# flipchip.net
KiCad netlist of a schematic drawn in EAGLE
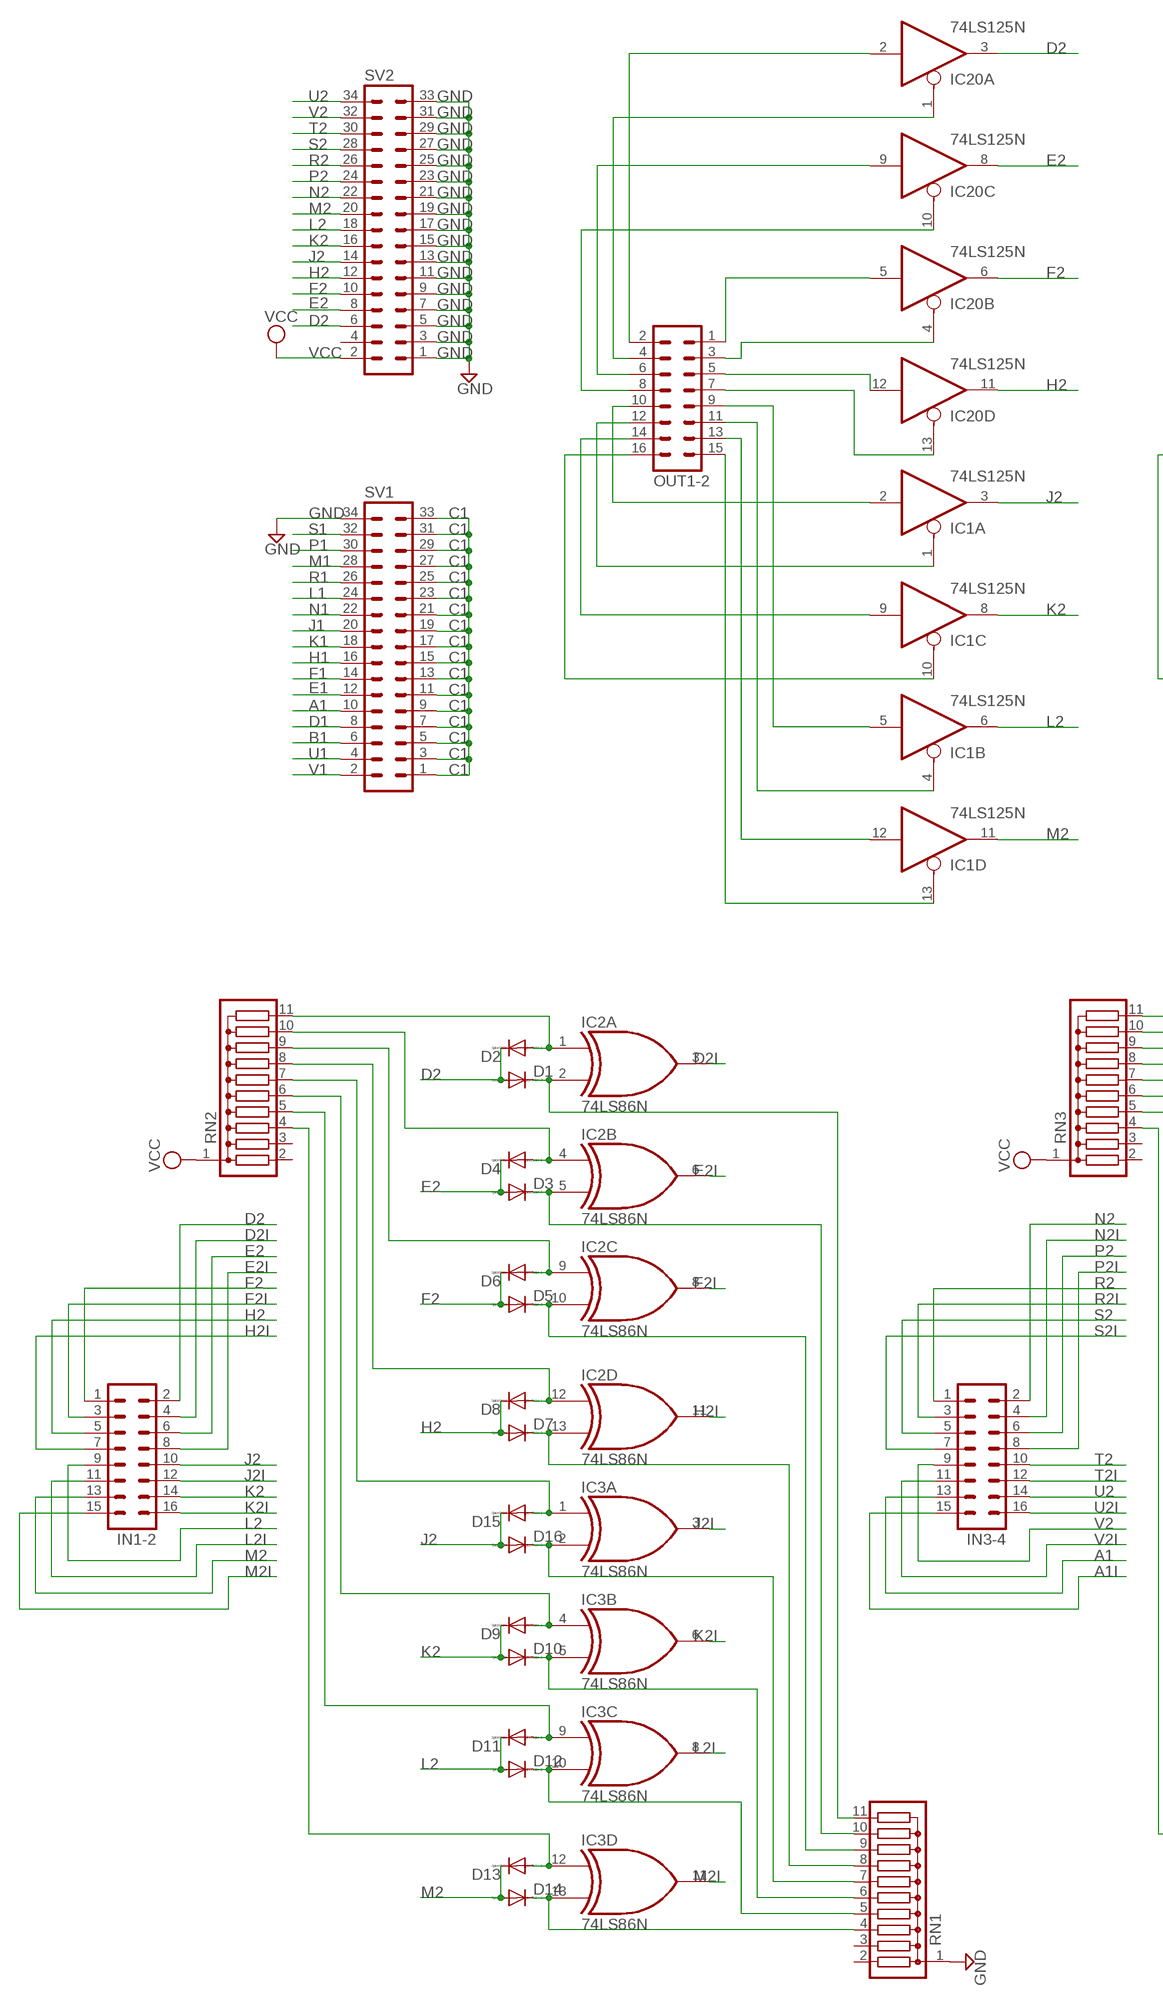
[diagram p0: schematic, sheet 1, part 1 of 2]
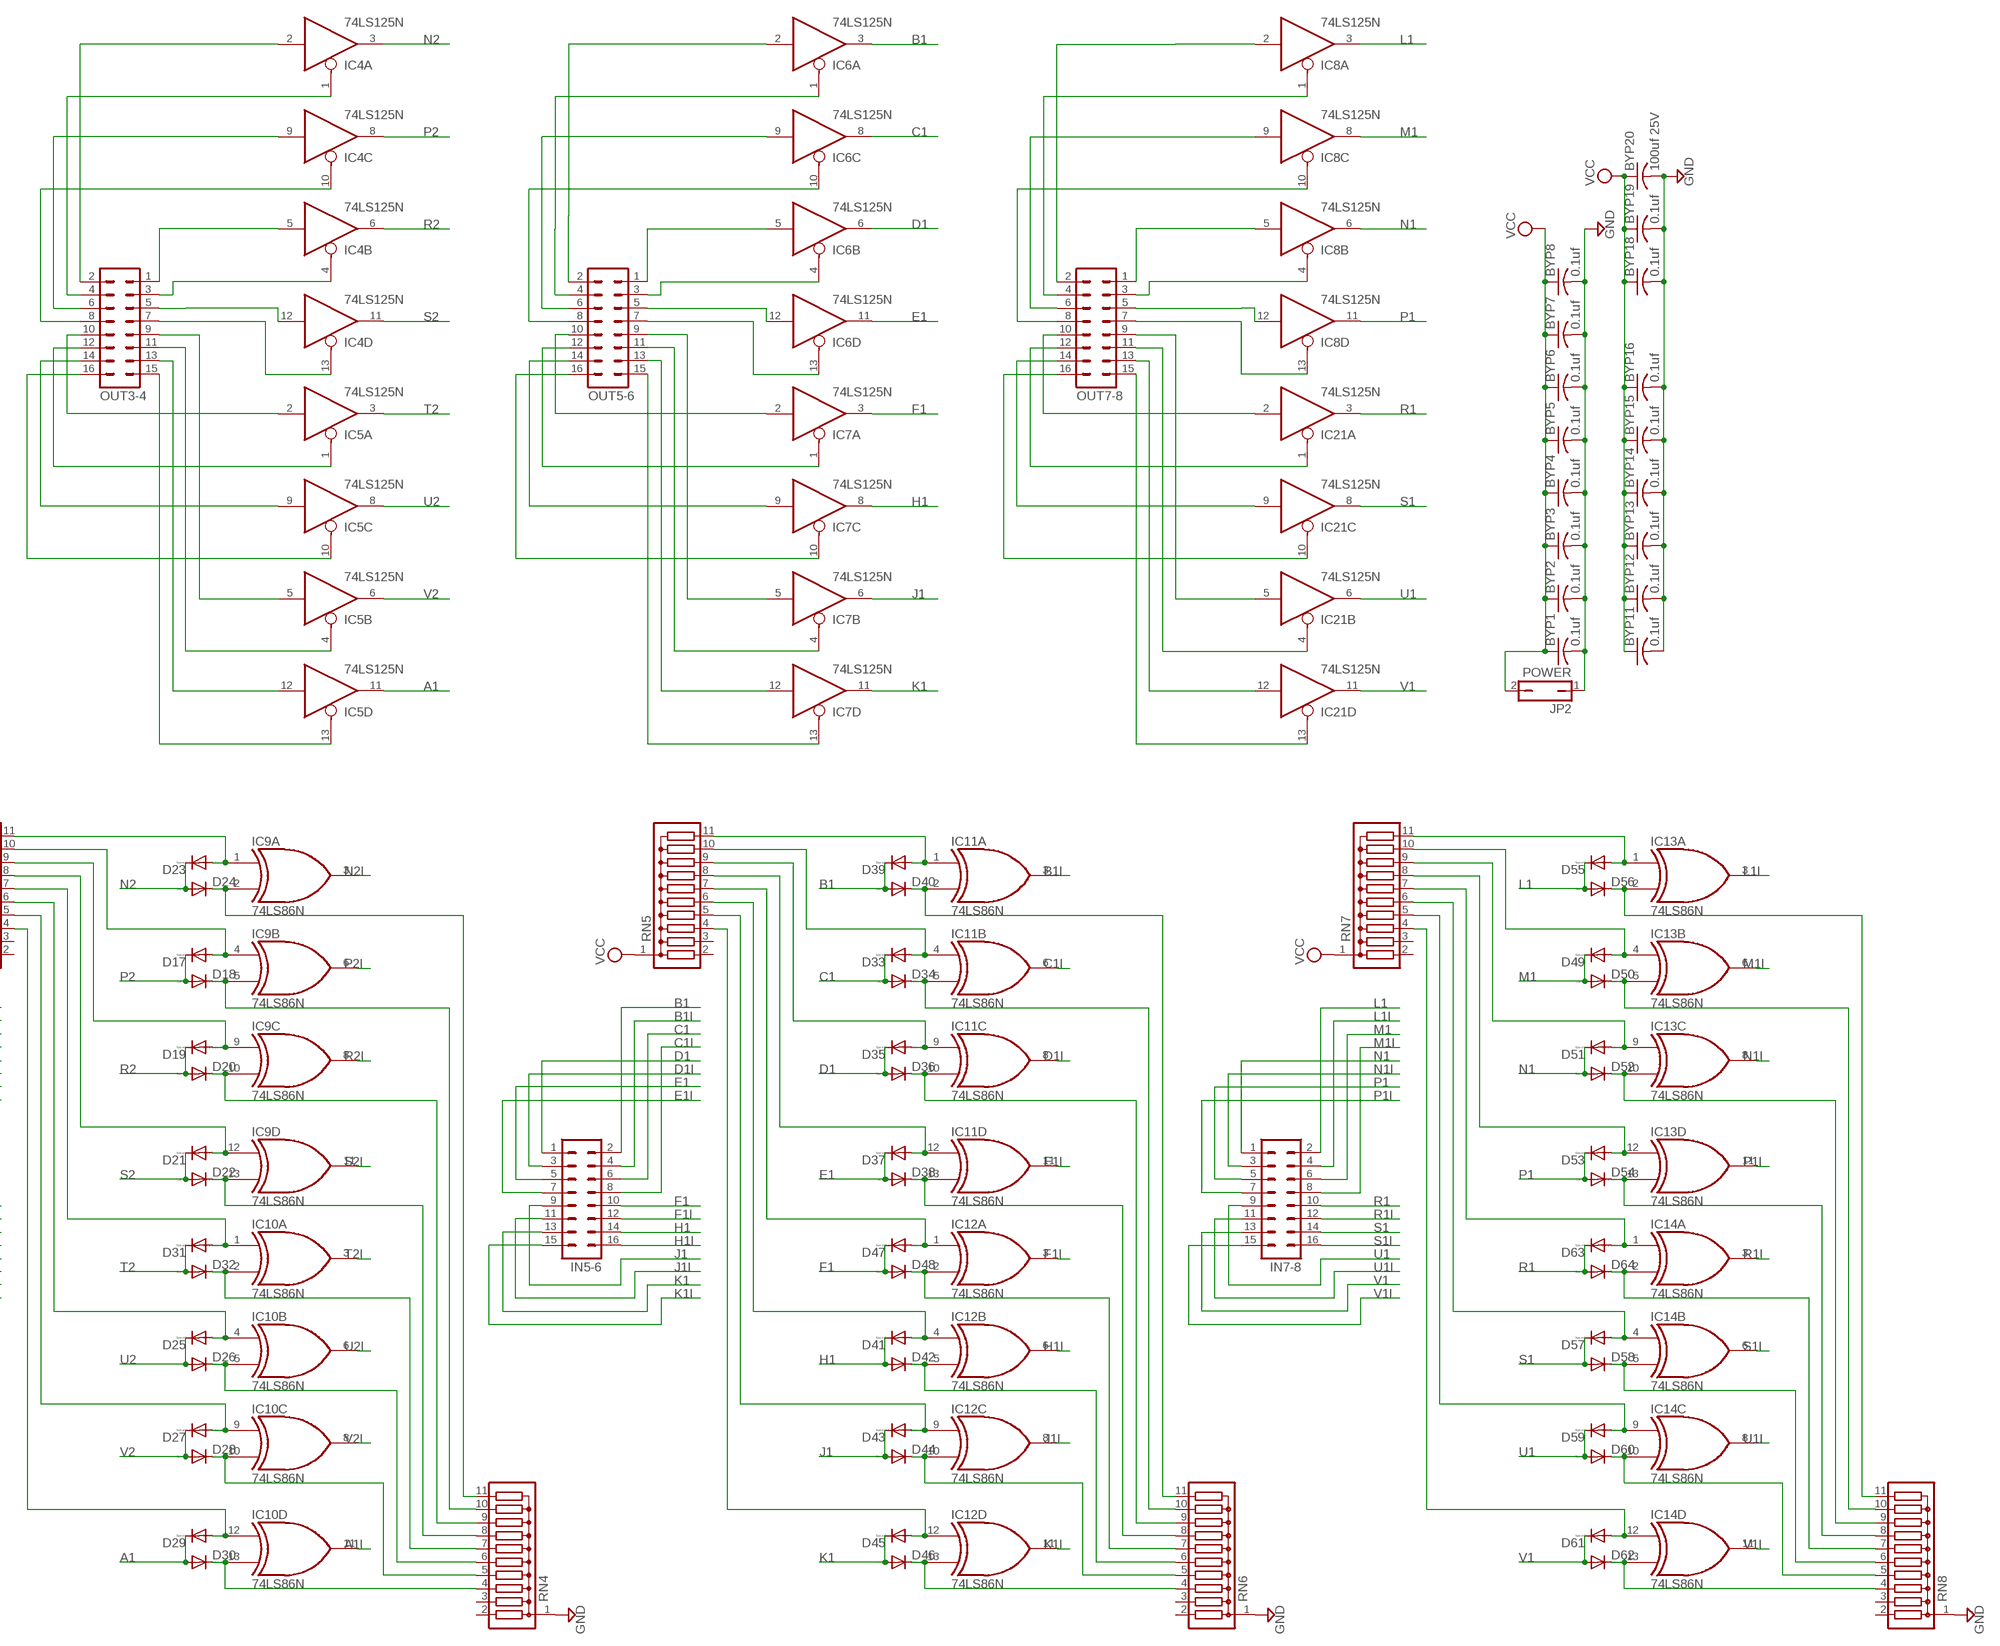
[diagram p1: schematic, sheet 1, part 2 of 2]

(export (version "E")
  (design (tool "Eeschema 10.0.6"))
  (components
    (comp (ref "BYP1")
      (value "0.1uf")
      (footprint "eagle-import:C050-025X075")
      (libsource (lib "eagle-import") (part "C-US050-025X075"))
    )
    (comp (ref "BYP2")
      (value "0.1uf")
      (footprint "eagle-import:C050-025X075")
      (libsource (lib "eagle-import") (part "C-US050-025X075"))
    )
    (comp (ref "BYP3")
      (value "0.1uf")
      (footprint "eagle-import:C050-025X075")
      (libsource (lib "eagle-import") (part "C-US050-025X075"))
    )
    (comp (ref "BYP4")
      (value "0.1uf")
      (footprint "eagle-import:C050-025X075")
      (libsource (lib "eagle-import") (part "C-US050-025X075"))
    )
    (comp (ref "BYP5")
      (value "0.1uf")
      (footprint "eagle-import:C050-025X075")
      (libsource (lib "eagle-import") (part "C-US050-025X075"))
    )
    (comp (ref "BYP6")
      (value "0.1uf")
      (footprint "eagle-import:C050-025X075")
      (libsource (lib "eagle-import") (part "C-US050-025X075"))
    )
    (comp (ref "BYP7")
      (value "0.1uf")
      (footprint "eagle-import:C050-025X075")
      (libsource (lib "eagle-import") (part "C-US050-025X075"))
    )
    (comp (ref "BYP8")
      (value "0.1uf")
      (footprint "eagle-import:C050-025X075")
      (libsource (lib "eagle-import") (part "C-US050-025X075"))
    )
    (comp (ref "BYP11")
      (value "0.1uf")
      (footprint "eagle-import:C050-025X075")
      (libsource (lib "eagle-import") (part "C-US050-025X075"))
    )
    (comp (ref "BYP12")
      (value "0.1uf")
      (footprint "eagle-import:C050-025X075")
      (libsource (lib "eagle-import") (part "C-US050-025X075"))
    )
    (comp (ref "BYP13")
      (value "0.1uf")
      (footprint "eagle-import:C050-025X075")
      (libsource (lib "eagle-import") (part "C-US050-025X075"))
    )
    (comp (ref "BYP14")
      (value "0.1uf")
      (footprint "eagle-import:C050-025X075")
      (libsource (lib "eagle-import") (part "C-US050-025X075"))
    )
    (comp (ref "BYP15")
      (value "0.1uf")
      (footprint "eagle-import:C050-025X075")
      (libsource (lib "eagle-import") (part "C-US050-025X075"))
    )
    (comp (ref "BYP16")
      (value "0.1uf")
      (footprint "eagle-import:C050-025X075")
      (libsource (lib "eagle-import") (part "C-US050-025X075"))
    )
    (comp (ref "BYP18")
      (value "0.1uf")
      (footprint "eagle-import:C050-025X075")
      (libsource (lib "eagle-import") (part "C-US050-025X075"))
    )
    (comp (ref "BYP19")
      (value "0.1uf")
      (footprint "eagle-import:C050-025X075")
      (libsource (lib "eagle-import") (part "C-US050-025X075"))
    )
    (comp (ref "BYP20")
      (value "100uf 25V")
      (footprint "eagle-import:C150-064X183")
      (libsource (lib "eagle-import") (part "C-US150-064X183"))
    )
    (comp (ref "D1")
      (value "DIODE-D-2.5")
      (footprint "eagle-import:D-2.5")
      (libsource (lib "eagle-import") (part "DIODE-D-2.5"))
    )
    (comp (ref "D2")
      (value "DIODE-D-2.5")
      (footprint "eagle-import:D-2.5")
      (libsource (lib "eagle-import") (part "DIODE-D-2.5"))
    )
    (comp (ref "D3")
      (value "DIODE-D-2.5")
      (footprint "eagle-import:D-2.5")
      (libsource (lib "eagle-import") (part "DIODE-D-2.5"))
    )
    (comp (ref "D4")
      (value "DIODE-D-2.5")
      (footprint "eagle-import:D-2.5")
      (libsource (lib "eagle-import") (part "DIODE-D-2.5"))
    )
    (comp (ref "D5")
      (value "DIODE-D-2.5")
      (footprint "eagle-import:D-2.5")
      (libsource (lib "eagle-import") (part "DIODE-D-2.5"))
    )
    (comp (ref "D6")
      (value "DIODE-D-2.5")
      (footprint "eagle-import:D-2.5")
      (libsource (lib "eagle-import") (part "DIODE-D-2.5"))
    )
    (comp (ref "D7")
      (value "DIODE-D-2.5")
      (footprint "eagle-import:D-2.5")
      (libsource (lib "eagle-import") (part "DIODE-D-2.5"))
    )
    (comp (ref "D8")
      (value "DIODE-D-2.5")
      (footprint "eagle-import:D-2.5")
      (libsource (lib "eagle-import") (part "DIODE-D-2.5"))
    )
    (comp (ref "D9")
      (value "DIODE-D-2.5")
      (footprint "eagle-import:D-2.5")
      (libsource (lib "eagle-import") (part "DIODE-D-2.5"))
    )
    (comp (ref "D10")
      (value "DIODE-D-2.5")
      (footprint "eagle-import:D-2.5")
      (libsource (lib "eagle-import") (part "DIODE-D-2.5"))
    )
    (comp (ref "D11")
      (value "DIODE-D-2.5")
      (footprint "eagle-import:D-2.5")
      (libsource (lib "eagle-import") (part "DIODE-D-2.5"))
    )
    (comp (ref "D12")
      (value "DIODE-D-2.5")
      (footprint "eagle-import:D-2.5")
      (libsource (lib "eagle-import") (part "DIODE-D-2.5"))
    )
    (comp (ref "D13")
      (value "DIODE-D-2.5")
      (footprint "eagle-import:D-2.5")
      (libsource (lib "eagle-import") (part "DIODE-D-2.5"))
    )
    (comp (ref "D14")
      (value "DIODE-D-2.5")
      (footprint "eagle-import:D-2.5")
      (libsource (lib "eagle-import") (part "DIODE-D-2.5"))
    )
    (comp (ref "D15")
      (value "DIODE-D-2.5")
      (footprint "eagle-import:D-2.5")
      (libsource (lib "eagle-import") (part "DIODE-D-2.5"))
    )
    (comp (ref "D16")
      (value "DIODE-D-2.5")
      (footprint "eagle-import:D-2.5")
      (libsource (lib "eagle-import") (part "DIODE-D-2.5"))
    )
    (comp (ref "D17")
      (value "DIODE-D-2.5")
      (footprint "eagle-import:D-2.5")
      (libsource (lib "eagle-import") (part "DIODE-D-2.5"))
    )
    (comp (ref "D18")
      (value "DIODE-D-2.5")
      (footprint "eagle-import:D-2.5")
      (libsource (lib "eagle-import") (part "DIODE-D-2.5"))
    )
    (comp (ref "D19")
      (value "DIODE-D-2.5")
      (footprint "eagle-import:D-2.5")
      (libsource (lib "eagle-import") (part "DIODE-D-2.5"))
    )
    (comp (ref "D20")
      (value "DIODE-D-2.5")
      (footprint "eagle-import:D-2.5")
      (libsource (lib "eagle-import") (part "DIODE-D-2.5"))
    )
    (comp (ref "D21")
      (value "DIODE-D-2.5")
      (footprint "eagle-import:D-2.5")
      (libsource (lib "eagle-import") (part "DIODE-D-2.5"))
    )
    (comp (ref "D22")
      (value "DIODE-D-2.5")
      (footprint "eagle-import:D-2.5")
      (libsource (lib "eagle-import") (part "DIODE-D-2.5"))
    )
    (comp (ref "D23")
      (value "DIODE-D-2.5")
      (footprint "eagle-import:D-2.5")
      (libsource (lib "eagle-import") (part "DIODE-D-2.5"))
    )
    (comp (ref "D24")
      (value "DIODE-D-2.5")
      (footprint "eagle-import:D-2.5")
      (libsource (lib "eagle-import") (part "DIODE-D-2.5"))
    )
    (comp (ref "D25")
      (value "DIODE-D-2.5")
      (footprint "eagle-import:D-2.5")
      (libsource (lib "eagle-import") (part "DIODE-D-2.5"))
    )
    (comp (ref "D26")
      (value "DIODE-D-2.5")
      (footprint "eagle-import:D-2.5")
      (libsource (lib "eagle-import") (part "DIODE-D-2.5"))
    )
    (comp (ref "D27")
      (value "DIODE-D-2.5")
      (footprint "eagle-import:D-2.5")
      (libsource (lib "eagle-import") (part "DIODE-D-2.5"))
    )
    (comp (ref "D28")
      (value "DIODE-D-2.5")
      (footprint "eagle-import:D-2.5")
      (libsource (lib "eagle-import") (part "DIODE-D-2.5"))
    )
    (comp (ref "D29")
      (value "DIODE-D-2.5")
      (footprint "eagle-import:D-2.5")
      (libsource (lib "eagle-import") (part "DIODE-D-2.5"))
    )
    (comp (ref "D30")
      (value "DIODE-D-2.5")
      (footprint "eagle-import:D-2.5")
      (libsource (lib "eagle-import") (part "DIODE-D-2.5"))
    )
    (comp (ref "D31")
      (value "DIODE-D-2.5")
      (footprint "eagle-import:D-2.5")
      (libsource (lib "eagle-import") (part "DIODE-D-2.5"))
    )
    (comp (ref "D32")
      (value "DIODE-D-2.5")
      (footprint "eagle-import:D-2.5")
      (libsource (lib "eagle-import") (part "DIODE-D-2.5"))
    )
    (comp (ref "D33")
      (value "DIODE-D-2.5")
      (footprint "eagle-import:D-2.5")
      (libsource (lib "eagle-import") (part "DIODE-D-2.5"))
    )
    (comp (ref "D34")
      (value "DIODE-D-2.5")
      (footprint "eagle-import:D-2.5")
      (libsource (lib "eagle-import") (part "DIODE-D-2.5"))
    )
    (comp (ref "D35")
      (value "DIODE-D-2.5")
      (footprint "eagle-import:D-2.5")
      (libsource (lib "eagle-import") (part "DIODE-D-2.5"))
    )
    (comp (ref "D36")
      (value "DIODE-D-2.5")
      (footprint "eagle-import:D-2.5")
      (libsource (lib "eagle-import") (part "DIODE-D-2.5"))
    )
    (comp (ref "D37")
      (value "DIODE-D-2.5")
      (footprint "eagle-import:D-2.5")
      (libsource (lib "eagle-import") (part "DIODE-D-2.5"))
    )
    (comp (ref "D38")
      (value "DIODE-D-2.5")
      (footprint "eagle-import:D-2.5")
      (libsource (lib "eagle-import") (part "DIODE-D-2.5"))
    )
    (comp (ref "D39")
      (value "DIODE-D-2.5")
      (footprint "eagle-import:D-2.5")
      (libsource (lib "eagle-import") (part "DIODE-D-2.5"))
    )
    (comp (ref "D40")
      (value "DIODE-D-2.5")
      (footprint "eagle-import:D-2.5")
      (libsource (lib "eagle-import") (part "DIODE-D-2.5"))
    )
    (comp (ref "D41")
      (value "DIODE-D-2.5")
      (footprint "eagle-import:D-2.5")
      (libsource (lib "eagle-import") (part "DIODE-D-2.5"))
    )
    (comp (ref "D42")
      (value "DIODE-D-2.5")
      (footprint "eagle-import:D-2.5")
      (libsource (lib "eagle-import") (part "DIODE-D-2.5"))
    )
    (comp (ref "D43")
      (value "DIODE-D-2.5")
      (footprint "eagle-import:D-2.5")
      (libsource (lib "eagle-import") (part "DIODE-D-2.5"))
    )
    (comp (ref "D44")
      (value "DIODE-D-2.5")
      (footprint "eagle-import:D-2.5")
      (libsource (lib "eagle-import") (part "DIODE-D-2.5"))
    )
    (comp (ref "D45")
      (value "DIODE-D-2.5")
      (footprint "eagle-import:D-2.5")
      (libsource (lib "eagle-import") (part "DIODE-D-2.5"))
    )
    (comp (ref "D46")
      (value "DIODE-D-2.5")
      (footprint "eagle-import:D-2.5")
      (libsource (lib "eagle-import") (part "DIODE-D-2.5"))
    )
    (comp (ref "D47")
      (value "DIODE-D-2.5")
      (footprint "eagle-import:D-2.5")
      (libsource (lib "eagle-import") (part "DIODE-D-2.5"))
    )
    (comp (ref "D48")
      (value "DIODE-D-2.5")
      (footprint "eagle-import:D-2.5")
      (libsource (lib "eagle-import") (part "DIODE-D-2.5"))
    )
    (comp (ref "D49")
      (value "DIODE-D-2.5")
      (footprint "eagle-import:D-2.5")
      (libsource (lib "eagle-import") (part "DIODE-D-2.5"))
    )
    (comp (ref "D50")
      (value "DIODE-D-2.5")
      (footprint "eagle-import:D-2.5")
      (libsource (lib "eagle-import") (part "DIODE-D-2.5"))
    )
    (comp (ref "D51")
      (value "DIODE-D-2.5")
      (footprint "eagle-import:D-2.5")
      (libsource (lib "eagle-import") (part "DIODE-D-2.5"))
    )
    (comp (ref "D52")
      (value "DIODE-D-2.5")
      (footprint "eagle-import:D-2.5")
      (libsource (lib "eagle-import") (part "DIODE-D-2.5"))
    )
    (comp (ref "D53")
      (value "DIODE-D-2.5")
      (footprint "eagle-import:D-2.5")
      (libsource (lib "eagle-import") (part "DIODE-D-2.5"))
    )
    (comp (ref "D54")
      (value "DIODE-D-2.5")
      (footprint "eagle-import:D-2.5")
      (libsource (lib "eagle-import") (part "DIODE-D-2.5"))
    )
    (comp (ref "D55")
      (value "DIODE-D-2.5")
      (footprint "eagle-import:D-2.5")
      (libsource (lib "eagle-import") (part "DIODE-D-2.5"))
    )
    (comp (ref "D56")
      (value "DIODE-D-2.5")
      (footprint "eagle-import:D-2.5")
      (libsource (lib "eagle-import") (part "DIODE-D-2.5"))
    )
    (comp (ref "D57")
      (value "DIODE-D-2.5")
      (footprint "eagle-import:D-2.5")
      (libsource (lib "eagle-import") (part "DIODE-D-2.5"))
    )
    (comp (ref "D58")
      (value "DIODE-D-2.5")
      (footprint "eagle-import:D-2.5")
      (libsource (lib "eagle-import") (part "DIODE-D-2.5"))
    )
    (comp (ref "D59")
      (value "DIODE-D-2.5")
      (footprint "eagle-import:D-2.5")
      (libsource (lib "eagle-import") (part "DIODE-D-2.5"))
    )
    (comp (ref "D60")
      (value "DIODE-D-2.5")
      (footprint "eagle-import:D-2.5")
      (libsource (lib "eagle-import") (part "DIODE-D-2.5"))
    )
    (comp (ref "D61")
      (value "DIODE-D-2.5")
      (footprint "eagle-import:D-2.5")
      (libsource (lib "eagle-import") (part "DIODE-D-2.5"))
    )
    (comp (ref "D62")
      (value "DIODE-D-2.5")
      (footprint "eagle-import:D-2.5")
      (libsource (lib "eagle-import") (part "DIODE-D-2.5"))
    )
    (comp (ref "D63")
      (value "DIODE-D-2.5")
      (footprint "eagle-import:D-2.5")
      (libsource (lib "eagle-import") (part "DIODE-D-2.5"))
    )
    (comp (ref "D64")
      (value "DIODE-D-2.5")
      (footprint "eagle-import:D-2.5")
      (libsource (lib "eagle-import") (part "DIODE-D-2.5"))
    )
    (comp (ref "IC1")
      (value "74LS125N")
      (footprint "eagle-import:DIL14")
      (libsource (lib "eagle-import") (part "74125NLS"))
    )
    (comp (ref "IC2")
      (value "74LS86N")
      (footprint "eagle-import:DIL14")
      (libsource (lib "eagle-import") (part "7486NLS"))
    )
    (comp (ref "IC3")
      (value "74LS86N")
      (footprint "eagle-import:DIL14")
      (libsource (lib "eagle-import") (part "7486NLS"))
    )
    (comp (ref "IC4")
      (value "74LS125N")
      (footprint "eagle-import:DIL14")
      (libsource (lib "eagle-import") (part "74125NLS"))
    )
    (comp (ref "IC5")
      (value "74LS125N")
      (footprint "eagle-import:DIL14")
      (libsource (lib "eagle-import") (part "74125NLS"))
    )
    (comp (ref "IC6")
      (value "74LS125N")
      (footprint "eagle-import:DIL14")
      (libsource (lib "eagle-import") (part "74125NLS"))
    )
    (comp (ref "IC7")
      (value "74LS125N")
      (footprint "eagle-import:DIL14")
      (libsource (lib "eagle-import") (part "74125NLS"))
    )
    (comp (ref "IC8")
      (value "74LS125N")
      (footprint "eagle-import:DIL14")
      (libsource (lib "eagle-import") (part "74125NLS"))
    )
    (comp (ref "IC9")
      (value "74LS86N")
      (footprint "eagle-import:DIL14")
      (libsource (lib "eagle-import") (part "7486NLS"))
    )
    (comp (ref "IC10")
      (value "74LS86N")
      (footprint "eagle-import:DIL14")
      (libsource (lib "eagle-import") (part "7486NLS"))
    )
    (comp (ref "IC11")
      (value "74LS86N")
      (footprint "eagle-import:DIL14")
      (libsource (lib "eagle-import") (part "7486NLS"))
    )
    (comp (ref "IC12")
      (value "74LS86N")
      (footprint "eagle-import:DIL14")
      (libsource (lib "eagle-import") (part "7486NLS"))
    )
    (comp (ref "IC13")
      (value "74LS86N")
      (footprint "eagle-import:DIL14")
      (libsource (lib "eagle-import") (part "7486NLS"))
    )
    (comp (ref "IC14")
      (value "74LS86N")
      (footprint "eagle-import:DIL14")
      (libsource (lib "eagle-import") (part "7486NLS"))
    )
    (comp (ref "IC20")
      (value "74LS125N")
      (footprint "eagle-import:DIL14")
      (libsource (lib "eagle-import") (part "74125NLS"))
    )
    (comp (ref "IC21")
      (value "74LS125N")
      (footprint "eagle-import:DIL14")
      (libsource (lib "eagle-import") (part "74125NLS"))
    )
    (comp (ref "IN1-2")
      (value "MA08-2")
      (footprint "eagle-import:MA08-2")
      (libsource (lib "eagle-import") (part "MA08-2"))
    )
    (comp (ref "IN3-4")
      (value "MA08-2")
      (footprint "eagle-import:MA08-2")
      (libsource (lib "eagle-import") (part "MA08-2"))
    )
    (comp (ref "IN5-6")
      (value "MA08-2")
      (footprint "eagle-import:MA08-2")
      (libsource (lib "eagle-import") (part "MA08-2"))
    )
    (comp (ref "IN7-8")
      (value "MA08-2")
      (footprint "eagle-import:MA08-2")
      (libsource (lib "eagle-import") (part "MA08-2"))
    )
    (comp (ref "JP2")
      (value "POWER")
      (footprint "eagle-import:JP1")
      (libsource (lib "eagle-import") (part "JP1Q"))
    )
    (comp (ref "OUT1-2")
      (value "MA08-2")
      (footprint "eagle-import:MA08-2")
      (libsource (lib "eagle-import") (part "MA08-2"))
    )
    (comp (ref "OUT3-4")
      (value "MA08-2")
      (footprint "eagle-import:MA08-2")
      (libsource (lib "eagle-import") (part "MA08-2"))
    )
    (comp (ref "OUT5-6")
      (value "MA08-2")
      (footprint "eagle-import:MA08-2")
      (libsource (lib "eagle-import") (part "MA08-2"))
    )
    (comp (ref "OUT7-8")
      (value "MA08-2")
      (footprint "eagle-import:MA08-2")
      (libsource (lib "eagle-import") (part "MA08-2"))
    )
    (comp (ref "RN1")
      (value "G10R")
      (footprint "eagle-import:SIL11")
      (libsource (lib "eagle-import") (part "G10R"))
    )
    (comp (ref "RN2")
      (value "G10R")
      (footprint "eagle-import:SIL11")
      (libsource (lib "eagle-import") (part "G10R"))
    )
    (comp (ref "RN3")
      (value "G10R")
      (footprint "eagle-import:SIL11")
      (libsource (lib "eagle-import") (part "G10R"))
    )
    (comp (ref "RN4")
      (value "G10R")
      (footprint "eagle-import:SIL11")
      (libsource (lib "eagle-import") (part "G10R"))
    )
    (comp (ref "RN5")
      (value "G10R")
      (footprint "eagle-import:SIL11")
      (libsource (lib "eagle-import") (part "G10R"))
    )
    (comp (ref "RN6")
      (value "G10R")
      (footprint "eagle-import:SIL11")
      (libsource (lib "eagle-import") (part "G10R"))
    )
    (comp (ref "RN7")
      (value "G10R")
      (footprint "eagle-import:SIL11")
      (libsource (lib "eagle-import") (part "G10R"))
    )
    (comp (ref "RN8")
      (value "G10R")
      (footprint "eagle-import:SIL11")
      (libsource (lib "eagle-import") (part "G10R"))
    )
    (comp (ref "SV1")
      (value "MA17-2")
      (footprint "eagle-import:MA17-2")
      (libsource (lib "eagle-import") (part "MA17-2"))
    )
    (comp (ref "SV2")
      (value "MA17-2")
      (footprint "eagle-import:MA17-2")
      (libsource (lib "eagle-import") (part "MA17-2"))
    )
  )
  (nets
    (net (code "1") (name "/A1") (class "Default")
      (node (ref "D29") (pin "C") (pinfunction "C_C") (pintype "passive"))
      (node (ref "D30") (pin "A") (pinfunction "A_A") (pintype "passive"))
      (node (ref "IC5") (pin "11") (pinfunction "O_11") (pintype "tri_state"))
      (node (ref "IN3-4") (pin "13") (pinfunction "13_13") (pintype "passive"))
      (node (ref "SV1") (pin "10") (pinfunction "10_10") (pintype "passive"))
    )
    (net (code "2") (name "/A1I") (class "Default")
      (node (ref "IC10") (pin "11") (pinfunction "O_11") (pintype "output"))
      (node (ref "IN3-4") (pin "15") (pinfunction "15_15") (pintype "passive"))
    )
    (net (code "3") (name "/B1") (class "Default")
      (node (ref "D39") (pin "C") (pinfunction "C_C") (pintype "passive"))
      (node (ref "D40") (pin "A") (pinfunction "A_A") (pintype "passive"))
      (node (ref "IC6") (pin "3") (pinfunction "O_3") (pintype "tri_state"))
      (node (ref "IN5-6") (pin "2") (pinfunction "2_2") (pintype "passive"))
      (node (ref "SV1") (pin "6") (pinfunction "6_6") (pintype "passive"))
    )
    (net (code "4") (name "/B1I") (class "Default")
      (node (ref "IC11") (pin "3") (pinfunction "O_3") (pintype "output"))
      (node (ref "IN5-6") (pin "4") (pinfunction "4_4") (pintype "passive"))
    )
    (net (code "5") (name "/C1") (class "Default")
      (node (ref "D33") (pin "C") (pinfunction "C_C") (pintype "passive"))
      (node (ref "D34") (pin "A") (pinfunction "A_A") (pintype "passive"))
      (node (ref "IC6") (pin "8") (pinfunction "O_8") (pintype "tri_state"))
      (node (ref "IN5-6") (pin "6") (pinfunction "6_6") (pintype "passive"))
      (node (ref "SV1") (pin "1") (pinfunction "1_1") (pintype "passive"))
      (node (ref "SV1") (pin "11") (pinfunction "11_11") (pintype "passive"))
      (node (ref "SV1") (pin "13") (pinfunction "13_13") (pintype "passive"))
      (node (ref "SV1") (pin "15") (pinfunction "15_15") (pintype "passive"))
      (node (ref "SV1") (pin "17") (pinfunction "17_17") (pintype "passive"))
      (node (ref "SV1") (pin "19") (pinfunction "19_19") (pintype "passive"))
      (node (ref "SV1") (pin "21") (pinfunction "21_21") (pintype "passive"))
      (node (ref "SV1") (pin "23") (pinfunction "23_23") (pintype "passive"))
      (node (ref "SV1") (pin "25") (pinfunction "25_25") (pintype "passive"))
      (node (ref "SV1") (pin "27") (pinfunction "27_27") (pintype "passive"))
      (node (ref "SV1") (pin "29") (pinfunction "29_29") (pintype "passive"))
      (node (ref "SV1") (pin "3") (pinfunction "3_3") (pintype "passive"))
      (node (ref "SV1") (pin "31") (pinfunction "31_31") (pintype "passive"))
      (node (ref "SV1") (pin "33") (pinfunction "33_33") (pintype "passive"))
      (node (ref "SV1") (pin "5") (pinfunction "5_5") (pintype "passive"))
      (node (ref "SV1") (pin "7") (pinfunction "7_7") (pintype "passive"))
      (node (ref "SV1") (pin "9") (pinfunction "9_9") (pintype "passive"))
    )
    (net (code "6") (name "/C1I") (class "Default")
      (node (ref "IC11") (pin "6") (pinfunction "O_6") (pintype "output"))
      (node (ref "IN5-6") (pin "8") (pinfunction "8_8") (pintype "passive"))
    )
    (net (code "7") (name "/D1") (class "Default")
      (node (ref "D35") (pin "C") (pinfunction "C_C") (pintype "passive"))
      (node (ref "D36") (pin "A") (pinfunction "A_A") (pintype "passive"))
      (node (ref "IC6") (pin "6") (pinfunction "O_6") (pintype "tri_state"))
      (node (ref "IN5-6") (pin "1") (pinfunction "1_1") (pintype "passive"))
      (node (ref "SV1") (pin "8") (pinfunction "8_8") (pintype "passive"))
    )
    (net (code "8") (name "/D1I") (class "Default")
      (node (ref "IC11") (pin "8") (pinfunction "O_8") (pintype "output"))
      (node (ref "IN5-6") (pin "3") (pinfunction "3_3") (pintype "passive"))
    )
    (net (code "9") (name "/D2") (class "Default")
      (node (ref "D1") (pin "A") (pinfunction "A_A") (pintype "passive"))
      (node (ref "D2") (pin "C") (pinfunction "C_C") (pintype "passive"))
      (node (ref "IC20") (pin "3") (pinfunction "O_3") (pintype "tri_state"))
      (node (ref "IN1-2") (pin "2") (pinfunction "2_2") (pintype "passive"))
      (node (ref "SV2") (pin "6") (pinfunction "6_6") (pintype "passive"))
    )
    (net (code "10") (name "/D2I") (class "Default")
      (node (ref "IC2") (pin "3") (pinfunction "O_3") (pintype "output"))
      (node (ref "IN1-2") (pin "4") (pinfunction "4_4") (pintype "passive"))
    )
    (net (code "11") (name "/E1") (class "Default")
      (node (ref "D37") (pin "C") (pinfunction "C_C") (pintype "passive"))
      (node (ref "D38") (pin "A") (pinfunction "A_A") (pintype "passive"))
      (node (ref "IC6") (pin "11") (pinfunction "O_11") (pintype "tri_state"))
      (node (ref "IN5-6") (pin "5") (pinfunction "5_5") (pintype "passive"))
      (node (ref "SV1") (pin "12") (pinfunction "12_12") (pintype "passive"))
    )
    (net (code "12") (name "/E1I") (class "Default")
      (node (ref "IC11") (pin "11") (pinfunction "O_11") (pintype "output"))
      (node (ref "IN5-6") (pin "7") (pinfunction "7_7") (pintype "passive"))
    )
    (net (code "13") (name "/E2") (class "Default")
      (node (ref "D3") (pin "A") (pinfunction "A_A") (pintype "passive"))
      (node (ref "D4") (pin "C") (pinfunction "C_C") (pintype "passive"))
      (node (ref "IC20") (pin "8") (pinfunction "O_8") (pintype "tri_state"))
      (node (ref "IN1-2") (pin "6") (pinfunction "6_6") (pintype "passive"))
      (node (ref "SV2") (pin "8") (pinfunction "8_8") (pintype "passive"))
    )
    (net (code "14") (name "/E2I") (class "Default")
      (node (ref "IC2") (pin "6") (pinfunction "O_6") (pintype "output"))
      (node (ref "IN1-2") (pin "8") (pinfunction "8_8") (pintype "passive"))
    )
    (net (code "15") (name "/F1") (class "Default")
      (node (ref "D47") (pin "C") (pinfunction "C_C") (pintype "passive"))
      (node (ref "D48") (pin "A") (pinfunction "A_A") (pintype "passive"))
      (node (ref "IC7") (pin "3") (pinfunction "O_3") (pintype "tri_state"))
      (node (ref "IN5-6") (pin "10") (pinfunction "10_10") (pintype "passive"))
      (node (ref "SV1") (pin "14") (pinfunction "14_14") (pintype "passive"))
    )
    (net (code "16") (name "/F1I") (class "Default")
      (node (ref "IC12") (pin "3") (pinfunction "O_3") (pintype "output"))
      (node (ref "IN5-6") (pin "12") (pinfunction "12_12") (pintype "passive"))
    )
    (net (code "17") (name "/F2") (class "Default")
      (node (ref "D5") (pin "A") (pinfunction "A_A") (pintype "passive"))
      (node (ref "D6") (pin "C") (pinfunction "C_C") (pintype "passive"))
      (node (ref "IC20") (pin "6") (pinfunction "O_6") (pintype "tri_state"))
      (node (ref "IN1-2") (pin "1") (pinfunction "1_1") (pintype "passive"))
      (node (ref "SV2") (pin "10") (pinfunction "10_10") (pintype "passive"))
    )
    (net (code "18") (name "/F2I") (class "Default")
      (node (ref "IC2") (pin "8") (pinfunction "O_8") (pintype "output"))
      (node (ref "IN1-2") (pin "3") (pinfunction "3_3") (pintype "passive"))
    )
    (net (code "19") (name "/H1") (class "Default")
      (node (ref "D41") (pin "C") (pinfunction "C_C") (pintype "passive"))
      (node (ref "D42") (pin "A") (pinfunction "A_A") (pintype "passive"))
      (node (ref "IC7") (pin "8") (pinfunction "O_8") (pintype "tri_state"))
      (node (ref "IN5-6") (pin "14") (pinfunction "14_14") (pintype "passive"))
      (node (ref "SV1") (pin "16") (pinfunction "16_16") (pintype "passive"))
    )
    (net (code "20") (name "/H1I") (class "Default")
      (node (ref "IC12") (pin "6") (pinfunction "O_6") (pintype "output"))
      (node (ref "IN5-6") (pin "16") (pinfunction "16_16") (pintype "passive"))
    )
    (net (code "21") (name "/H2") (class "Default")
      (node (ref "D7") (pin "A") (pinfunction "A_A") (pintype "passive"))
      (node (ref "D8") (pin "C") (pinfunction "C_C") (pintype "passive"))
      (node (ref "IC20") (pin "11") (pinfunction "O_11") (pintype "tri_state"))
      (node (ref "IN1-2") (pin "5") (pinfunction "5_5") (pintype "passive"))
      (node (ref "SV2") (pin "12") (pinfunction "12_12") (pintype "passive"))
    )
    (net (code "22") (name "/H2I") (class "Default")
      (node (ref "IC2") (pin "11") (pinfunction "O_11") (pintype "output"))
      (node (ref "IN1-2") (pin "7") (pinfunction "7_7") (pintype "passive"))
    )
    (net (code "23") (name "/J1") (class "Default")
      (node (ref "D43") (pin "C") (pinfunction "C_C") (pintype "passive"))
      (node (ref "D44") (pin "A") (pinfunction "A_A") (pintype "passive"))
      (node (ref "IC7") (pin "6") (pinfunction "O_6") (pintype "tri_state"))
      (node (ref "IN5-6") (pin "9") (pinfunction "9_9") (pintype "passive"))
      (node (ref "SV1") (pin "20") (pinfunction "20_20") (pintype "passive"))
    )
    (net (code "24") (name "/J1I") (class "Default")
      (node (ref "IC12") (pin "8") (pinfunction "O_8") (pintype "output"))
      (node (ref "IN5-6") (pin "11") (pinfunction "11_11") (pintype "passive"))
    )
    (net (code "25") (name "/J2") (class "Default")
      (node (ref "D15") (pin "C") (pinfunction "C_C") (pintype "passive"))
      (node (ref "D16") (pin "A") (pinfunction "A_A") (pintype "passive"))
      (node (ref "IC1") (pin "3") (pinfunction "O_3") (pintype "tri_state"))
      (node (ref "IN1-2") (pin "10") (pinfunction "10_10") (pintype "passive"))
      (node (ref "SV2") (pin "14") (pinfunction "14_14") (pintype "passive"))
    )
    (net (code "26") (name "/J2I") (class "Default")
      (node (ref "IC3") (pin "3") (pinfunction "O_3") (pintype "output"))
      (node (ref "IN1-2") (pin "12") (pinfunction "12_12") (pintype "passive"))
    )
    (net (code "27") (name "/K1") (class "Default")
      (node (ref "D45") (pin "C") (pinfunction "C_C") (pintype "passive"))
      (node (ref "D46") (pin "A") (pinfunction "A_A") (pintype "passive"))
      (node (ref "IC7") (pin "11") (pinfunction "O_11") (pintype "tri_state"))
      (node (ref "IN5-6") (pin "13") (pinfunction "13_13") (pintype "passive"))
      (node (ref "SV1") (pin "18") (pinfunction "18_18") (pintype "passive"))
    )
    (net (code "28") (name "/K1I") (class "Default")
      (node (ref "IC12") (pin "11") (pinfunction "O_11") (pintype "output"))
      (node (ref "IN5-6") (pin "15") (pinfunction "15_15") (pintype "passive"))
    )
    (net (code "29") (name "/K2") (class "Default")
      (node (ref "D10") (pin "A") (pinfunction "A_A") (pintype "passive"))
      (node (ref "D9") (pin "C") (pinfunction "C_C") (pintype "passive"))
      (node (ref "IC1") (pin "8") (pinfunction "O_8") (pintype "tri_state"))
      (node (ref "IN1-2") (pin "14") (pinfunction "14_14") (pintype "passive"))
      (node (ref "SV2") (pin "16") (pinfunction "16_16") (pintype "passive"))
    )
    (net (code "30") (name "/K2I") (class "Default")
      (node (ref "IC3") (pin "6") (pinfunction "O_6") (pintype "output"))
      (node (ref "IN1-2") (pin "16") (pinfunction "16_16") (pintype "passive"))
    )
    (net (code "31") (name "/L1") (class "Default")
      (node (ref "D55") (pin "C") (pinfunction "C_C") (pintype "passive"))
      (node (ref "D56") (pin "A") (pinfunction "A_A") (pintype "passive"))
      (node (ref "IC8") (pin "3") (pinfunction "O_3") (pintype "tri_state"))
      (node (ref "IN7-8") (pin "2") (pinfunction "2_2") (pintype "passive"))
      (node (ref "SV1") (pin "24") (pinfunction "24_24") (pintype "passive"))
    )
    (net (code "32") (name "/L1I") (class "Default")
      (node (ref "IC13") (pin "3") (pinfunction "O_3") (pintype "output"))
      (node (ref "IN7-8") (pin "4") (pinfunction "4_4") (pintype "passive"))
    )
    (net (code "33") (name "/L2") (class "Default")
      (node (ref "D11") (pin "C") (pinfunction "C_C") (pintype "passive"))
      (node (ref "D12") (pin "A") (pinfunction "A_A") (pintype "passive"))
      (node (ref "IC1") (pin "6") (pinfunction "O_6") (pintype "tri_state"))
      (node (ref "IN1-2") (pin "9") (pinfunction "9_9") (pintype "passive"))
      (node (ref "SV2") (pin "18") (pinfunction "18_18") (pintype "passive"))
    )
    (net (code "34") (name "/L2I") (class "Default")
      (node (ref "IC3") (pin "8") (pinfunction "O_8") (pintype "output"))
      (node (ref "IN1-2") (pin "11") (pinfunction "11_11") (pintype "passive"))
    )
    (net (code "35") (name "/M1") (class "Default")
      (node (ref "D49") (pin "C") (pinfunction "C_C") (pintype "passive"))
      (node (ref "D50") (pin "A") (pinfunction "A_A") (pintype "passive"))
      (node (ref "IC8") (pin "8") (pinfunction "O_8") (pintype "tri_state"))
      (node (ref "IN7-8") (pin "6") (pinfunction "6_6") (pintype "passive"))
      (node (ref "SV1") (pin "28") (pinfunction "28_28") (pintype "passive"))
    )
    (net (code "36") (name "/M1I") (class "Default")
      (node (ref "IC13") (pin "6") (pinfunction "O_6") (pintype "output"))
      (node (ref "IN7-8") (pin "8") (pinfunction "8_8") (pintype "passive"))
    )
    (net (code "37") (name "/M2") (class "Default")
      (node (ref "D13") (pin "C") (pinfunction "C_C") (pintype "passive"))
      (node (ref "D14") (pin "A") (pinfunction "A_A") (pintype "passive"))
      (node (ref "IC1") (pin "11") (pinfunction "O_11") (pintype "tri_state"))
      (node (ref "IN1-2") (pin "13") (pinfunction "13_13") (pintype "passive"))
      (node (ref "SV2") (pin "20") (pinfunction "20_20") (pintype "passive"))
    )
    (net (code "38") (name "/M2I") (class "Default")
      (node (ref "IC3") (pin "11") (pinfunction "O_11") (pintype "output"))
      (node (ref "IN1-2") (pin "15") (pinfunction "15_15") (pintype "passive"))
    )
    (net (code "39") (name "/N1") (class "Default")
      (node (ref "D51") (pin "C") (pinfunction "C_C") (pintype "passive"))
      (node (ref "D52") (pin "A") (pinfunction "A_A") (pintype "passive"))
      (node (ref "IC8") (pin "6") (pinfunction "O_6") (pintype "tri_state"))
      (node (ref "IN7-8") (pin "1") (pinfunction "1_1") (pintype "passive"))
      (node (ref "SV1") (pin "22") (pinfunction "22_22") (pintype "passive"))
    )
    (net (code "40") (name "/N1I") (class "Default")
      (node (ref "IC13") (pin "8") (pinfunction "O_8") (pintype "output"))
      (node (ref "IN7-8") (pin "3") (pinfunction "3_3") (pintype "passive"))
    )
    (net (code "41") (name "/N2") (class "Default")
      (node (ref "D23") (pin "C") (pinfunction "C_C") (pintype "passive"))
      (node (ref "D24") (pin "A") (pinfunction "A_A") (pintype "passive"))
      (node (ref "IC4") (pin "3") (pinfunction "O_3") (pintype "tri_state"))
      (node (ref "IN3-4") (pin "2") (pinfunction "2_2") (pintype "passive"))
      (node (ref "SV2") (pin "22") (pinfunction "22_22") (pintype "passive"))
    )
    (net (code "42") (name "/N2I") (class "Default")
      (node (ref "IC9") (pin "3") (pinfunction "O_3") (pintype "output"))
      (node (ref "IN3-4") (pin "4") (pinfunction "4_4") (pintype "passive"))
    )
    (net (code "43") (name "/P1") (class "Default")
      (node (ref "D53") (pin "C") (pinfunction "C_C") (pintype "passive"))
      (node (ref "D54") (pin "A") (pinfunction "A_A") (pintype "passive"))
      (node (ref "IC8") (pin "11") (pinfunction "O_11") (pintype "tri_state"))
      (node (ref "IN7-8") (pin "5") (pinfunction "5_5") (pintype "passive"))
      (node (ref "SV1") (pin "30") (pinfunction "30_30") (pintype "passive"))
    )
    (net (code "44") (name "/P1I") (class "Default")
      (node (ref "IC13") (pin "11") (pinfunction "O_11") (pintype "output"))
      (node (ref "IN7-8") (pin "7") (pinfunction "7_7") (pintype "passive"))
    )
    (net (code "45") (name "/P2") (class "Default")
      (node (ref "D17") (pin "C") (pinfunction "C_C") (pintype "passive"))
      (node (ref "D18") (pin "A") (pinfunction "A_A") (pintype "passive"))
      (node (ref "IC4") (pin "8") (pinfunction "O_8") (pintype "tri_state"))
      (node (ref "IN3-4") (pin "6") (pinfunction "6_6") (pintype "passive"))
      (node (ref "SV2") (pin "24") (pinfunction "24_24") (pintype "passive"))
    )
    (net (code "46") (name "/P2I") (class "Default")
      (node (ref "IC9") (pin "6") (pinfunction "O_6") (pintype "output"))
      (node (ref "IN3-4") (pin "8") (pinfunction "8_8") (pintype "passive"))
    )
    (net (code "47") (name "/R1") (class "Default")
      (node (ref "D63") (pin "C") (pinfunction "C_C") (pintype "passive"))
      (node (ref "D64") (pin "A") (pinfunction "A_A") (pintype "passive"))
      (node (ref "IC21") (pin "3") (pinfunction "O_3") (pintype "tri_state"))
      (node (ref "IN7-8") (pin "10") (pinfunction "10_10") (pintype "passive"))
      (node (ref "SV1") (pin "26") (pinfunction "26_26") (pintype "passive"))
    )
    (net (code "48") (name "/R1I") (class "Default")
      (node (ref "IC14") (pin "3") (pinfunction "O_3") (pintype "output"))
      (node (ref "IN7-8") (pin "12") (pinfunction "12_12") (pintype "passive"))
    )
    (net (code "49") (name "/R2") (class "Default")
      (node (ref "D19") (pin "C") (pinfunction "C_C") (pintype "passive"))
      (node (ref "D20") (pin "A") (pinfunction "A_A") (pintype "passive"))
      (node (ref "IC4") (pin "6") (pinfunction "O_6") (pintype "tri_state"))
      (node (ref "IN3-4") (pin "1") (pinfunction "1_1") (pintype "passive"))
      (node (ref "SV2") (pin "26") (pinfunction "26_26") (pintype "passive"))
    )
    (net (code "50") (name "/R2I") (class "Default")
      (node (ref "IC9") (pin "8") (pinfunction "O_8") (pintype "output"))
      (node (ref "IN3-4") (pin "3") (pinfunction "3_3") (pintype "passive"))
    )
    (net (code "51") (name "/S1") (class "Default")
      (node (ref "D57") (pin "C") (pinfunction "C_C") (pintype "passive"))
      (node (ref "D58") (pin "A") (pinfunction "A_A") (pintype "passive"))
      (node (ref "IC21") (pin "8") (pinfunction "O_8") (pintype "tri_state"))
      (node (ref "IN7-8") (pin "14") (pinfunction "14_14") (pintype "passive"))
      (node (ref "SV1") (pin "32") (pinfunction "32_32") (pintype "passive"))
    )
    (net (code "52") (name "/S1I") (class "Default")
      (node (ref "IC14") (pin "6") (pinfunction "O_6") (pintype "output"))
      (node (ref "IN7-8") (pin "16") (pinfunction "16_16") (pintype "passive"))
    )
    (net (code "53") (name "/S2") (class "Default")
      (node (ref "D21") (pin "C") (pinfunction "C_C") (pintype "passive"))
      (node (ref "D22") (pin "A") (pinfunction "A_A") (pintype "passive"))
      (node (ref "IC4") (pin "11") (pinfunction "O_11") (pintype "tri_state"))
      (node (ref "IN3-4") (pin "5") (pinfunction "5_5") (pintype "passive"))
      (node (ref "SV2") (pin "28") (pinfunction "28_28") (pintype "passive"))
    )
    (net (code "54") (name "/S2I") (class "Default")
      (node (ref "IC9") (pin "11") (pinfunction "O_11") (pintype "output"))
      (node (ref "IN3-4") (pin "7") (pinfunction "7_7") (pintype "passive"))
    )
    (net (code "55") (name "/T2") (class "Default")
      (node (ref "D31") (pin "C") (pinfunction "C_C") (pintype "passive"))
      (node (ref "D32") (pin "A") (pinfunction "A_A") (pintype "passive"))
      (node (ref "IC5") (pin "3") (pinfunction "O_3") (pintype "tri_state"))
      (node (ref "IN3-4") (pin "10") (pinfunction "10_10") (pintype "passive"))
      (node (ref "SV2") (pin "30") (pinfunction "30_30") (pintype "passive"))
    )
    (net (code "56") (name "/T2I") (class "Default")
      (node (ref "IC10") (pin "3") (pinfunction "O_3") (pintype "output"))
      (node (ref "IN3-4") (pin "12") (pinfunction "12_12") (pintype "passive"))
    )
    (net (code "57") (name "/U1") (class "Default")
      (node (ref "D59") (pin "C") (pinfunction "C_C") (pintype "passive"))
      (node (ref "D60") (pin "A") (pinfunction "A_A") (pintype "passive"))
      (node (ref "IC21") (pin "6") (pinfunction "O_6") (pintype "tri_state"))
      (node (ref "IN7-8") (pin "9") (pinfunction "9_9") (pintype "passive"))
      (node (ref "SV1") (pin "4") (pinfunction "4_4") (pintype "passive"))
    )
    (net (code "58") (name "/U1I") (class "Default")
      (node (ref "IC14") (pin "8") (pinfunction "O_8") (pintype "output"))
      (node (ref "IN7-8") (pin "11") (pinfunction "11_11") (pintype "passive"))
    )
    (net (code "59") (name "/U2") (class "Default")
      (node (ref "D25") (pin "C") (pinfunction "C_C") (pintype "passive"))
      (node (ref "D26") (pin "A") (pinfunction "A_A") (pintype "passive"))
      (node (ref "IC5") (pin "8") (pinfunction "O_8") (pintype "tri_state"))
      (node (ref "IN3-4") (pin "14") (pinfunction "14_14") (pintype "passive"))
      (node (ref "SV2") (pin "34") (pinfunction "34_34") (pintype "passive"))
    )
    (net (code "60") (name "/U2I") (class "Default")
      (node (ref "IC10") (pin "6") (pinfunction "O_6") (pintype "output"))
      (node (ref "IN3-4") (pin "16") (pinfunction "16_16") (pintype "passive"))
    )
    (net (code "61") (name "/V1") (class "Default")
      (node (ref "D61") (pin "C") (pinfunction "C_C") (pintype "passive"))
      (node (ref "D62") (pin "A") (pinfunction "A_A") (pintype "passive"))
      (node (ref "IC21") (pin "11") (pinfunction "O_11") (pintype "tri_state"))
      (node (ref "IN7-8") (pin "13") (pinfunction "13_13") (pintype "passive"))
      (node (ref "SV1") (pin "2") (pinfunction "2_2") (pintype "passive"))
    )
    (net (code "62") (name "/V1I") (class "Default")
      (node (ref "IC14") (pin "11") (pinfunction "O_11") (pintype "output"))
      (node (ref "IN7-8") (pin "15") (pinfunction "15_15") (pintype "passive"))
    )
    (net (code "63") (name "/V2") (class "Default")
      (node (ref "D27") (pin "C") (pinfunction "C_C") (pintype "passive"))
      (node (ref "D28") (pin "A") (pinfunction "A_A") (pintype "passive"))
      (node (ref "IC5") (pin "6") (pinfunction "O_6") (pintype "tri_state"))
      (node (ref "IN3-4") (pin "9") (pinfunction "9_9") (pintype "passive"))
      (node (ref "SV2") (pin "32") (pinfunction "32_32") (pintype "passive"))
    )
    (net (code "64") (name "/V2I") (class "Default")
      (node (ref "IC10") (pin "8") (pinfunction "O_8") (pintype "output"))
      (node (ref "IN3-4") (pin "11") (pinfunction "11_11") (pintype "passive"))
    )
    (net (code "65") (name "GND") (class "Default")
      (node (ref "BYP1") (pin "2") (pinfunction "2_2") (pintype "passive"))
      (node (ref "BYP11") (pin "2") (pinfunction "2_2") (pintype "passive"))
      (node (ref "BYP12") (pin "2") (pinfunction "2_2") (pintype "passive"))
      (node (ref "BYP13") (pin "2") (pinfunction "2_2") (pintype "passive"))
      (node (ref "BYP14") (pin "2") (pinfunction "2_2") (pintype "passive"))
      (node (ref "BYP15") (pin "2") (pinfunction "2_2") (pintype "passive"))
      (node (ref "BYP16") (pin "2") (pinfunction "2_2") (pintype "passive"))
      (node (ref "BYP18") (pin "2") (pinfunction "2_2") (pintype "passive"))
      (node (ref "BYP19") (pin "2") (pinfunction "2_2") (pintype "passive"))
      (node (ref "BYP2") (pin "2") (pinfunction "2_2") (pintype "passive"))
      (node (ref "BYP20") (pin "2") (pinfunction "2_2") (pintype "passive"))
      (node (ref "BYP3") (pin "2") (pinfunction "2_2") (pintype "passive"))
      (node (ref "BYP4") (pin "2") (pinfunction "2_2") (pintype "passive"))
      (node (ref "BYP5") (pin "2") (pinfunction "2_2") (pintype "passive"))
      (node (ref "BYP6") (pin "2") (pinfunction "2_2") (pintype "passive"))
      (node (ref "BYP7") (pin "2") (pinfunction "2_2") (pintype "passive"))
      (node (ref "BYP8") (pin "2") (pinfunction "2_2") (pintype "passive"))
      (node (ref "JP2") (pin "1") (pinfunction "1_1") (pintype "passive"))
      (node (ref "RN1") (pin "1") (pinfunction "1_1") (pintype "passive"))
      (node (ref "RN4") (pin "1") (pinfunction "1_1") (pintype "passive"))
      (node (ref "RN6") (pin "1") (pinfunction "1_1") (pintype "passive"))
      (node (ref "RN8") (pin "1") (pinfunction "1_1") (pintype "passive"))
      (node (ref "SV1") (pin "34") (pinfunction "34_34") (pintype "passive"))
      (node (ref "SV2") (pin "1") (pinfunction "1_1") (pintype "passive"))
      (node (ref "SV2") (pin "11") (pinfunction "11_11") (pintype "passive"))
      (node (ref "SV2") (pin "13") (pinfunction "13_13") (pintype "passive"))
      (node (ref "SV2") (pin "15") (pinfunction "15_15") (pintype "passive"))
      (node (ref "SV2") (pin "17") (pinfunction "17_17") (pintype "passive"))
      (node (ref "SV2") (pin "19") (pinfunction "19_19") (pintype "passive"))
      (node (ref "SV2") (pin "21") (pinfunction "21_21") (pintype "passive"))
      (node (ref "SV2") (pin "23") (pinfunction "23_23") (pintype "passive"))
      (node (ref "SV2") (pin "25") (pinfunction "25_25") (pintype "passive"))
      (node (ref "SV2") (pin "27") (pinfunction "27_27") (pintype "passive"))
      (node (ref "SV2") (pin "29") (pinfunction "29_29") (pintype "passive"))
      (node (ref "SV2") (pin "3") (pinfunction "3_3") (pintype "passive"))
      (node (ref "SV2") (pin "31") (pinfunction "31_31") (pintype "passive"))
      (node (ref "SV2") (pin "33") (pinfunction "33_33") (pintype "passive"))
      (node (ref "SV2") (pin "5") (pinfunction "5_5") (pintype "passive"))
      (node (ref "SV2") (pin "7") (pinfunction "7_7") (pintype "passive"))
      (node (ref "SV2") (pin "9") (pinfunction "9_9") (pintype "passive"))
    )
    (net (code "66") (name "Net-(IC1A-I)") (class "Default")
      (node (ref "IC1") (pin "2") (pinfunction "I_2") (pintype "input"))
      (node (ref "OUT1-2") (pin "10") (pinfunction "10_10") (pintype "passive"))
    )
    (net (code "67") (name "Net-(IC1A-OE)") (class "Default")
      (node (ref "IC1") (pin "1") (pinfunction "OE_1") (pintype "input"))
      (node (ref "OUT1-2") (pin "12") (pinfunction "12_12") (pintype "passive"))
    )
    (net (code "68") (name "Net-(IC1B-I)") (class "Default")
      (node (ref "IC1") (pin "5") (pinfunction "I_5") (pintype "input"))
      (node (ref "OUT1-2") (pin "9") (pinfunction "9_9") (pintype "passive"))
    )
    (net (code "69") (name "Net-(IC1B-OE)") (class "Default")
      (node (ref "IC1") (pin "4") (pinfunction "OE_4") (pintype "input"))
      (node (ref "OUT1-2") (pin "11") (pinfunction "11_11") (pintype "passive"))
    )
    (net (code "70") (name "Net-(IC1C-I)") (class "Default")
      (node (ref "IC1") (pin "9") (pinfunction "I_9") (pintype "input"))
      (node (ref "OUT1-2") (pin "14") (pinfunction "14_14") (pintype "passive"))
    )
    (net (code "71") (name "Net-(IC1C-OE)") (class "Default")
      (node (ref "IC1") (pin "10") (pinfunction "OE_10") (pintype "input"))
      (node (ref "OUT1-2") (pin "16") (pinfunction "16_16") (pintype "passive"))
    )
    (net (code "72") (name "Net-(IC1D-I)") (class "Default")
      (node (ref "IC1") (pin "12") (pinfunction "I_12") (pintype "input"))
      (node (ref "OUT1-2") (pin "13") (pinfunction "13_13") (pintype "passive"))
    )
    (net (code "73") (name "Net-(IC1D-OE)") (class "Default")
      (node (ref "IC1") (pin "13") (pinfunction "OE_13") (pintype "input"))
      (node (ref "OUT1-2") (pin "15") (pinfunction "15_15") (pintype "passive"))
    )
    (net (code "74") (name "Net-(IC2A-I0)") (class "Default")
      (node (ref "D2") (pin "A") (pinfunction "A_A") (pintype "passive"))
      (node (ref "IC2") (pin "1") (pinfunction "I0_1") (pintype "input"))
      (node (ref "RN2") (pin "11") (pinfunction "11_11") (pintype "passive"))
    )
    (net (code "75") (name "Net-(IC2A-I1)") (class "Default")
      (node (ref "D1") (pin "C") (pinfunction "C_C") (pintype "passive"))
      (node (ref "IC2") (pin "2") (pinfunction "I1_2") (pintype "input"))
      (node (ref "RN1") (pin "11") (pinfunction "11_11") (pintype "passive"))
    )
    (net (code "76") (name "Net-(IC2B-I0)") (class "Default")
      (node (ref "D4") (pin "A") (pinfunction "A_A") (pintype "passive"))
      (node (ref "IC2") (pin "4") (pinfunction "I0_4") (pintype "input"))
      (node (ref "RN2") (pin "10") (pinfunction "10_10") (pintype "passive"))
    )
    (net (code "77") (name "Net-(IC2B-I1)") (class "Default")
      (node (ref "D3") (pin "C") (pinfunction "C_C") (pintype "passive"))
      (node (ref "IC2") (pin "5") (pinfunction "I1_5") (pintype "input"))
      (node (ref "RN1") (pin "10") (pinfunction "10_10") (pintype "passive"))
    )
    (net (code "78") (name "Net-(IC2C-I0)") (class "Default")
      (node (ref "D6") (pin "A") (pinfunction "A_A") (pintype "passive"))
      (node (ref "IC2") (pin "9") (pinfunction "I0_9") (pintype "input"))
      (node (ref "RN2") (pin "9") (pinfunction "9_9") (pintype "passive"))
    )
    (net (code "79") (name "Net-(IC2C-I1)") (class "Default")
      (node (ref "D5") (pin "C") (pinfunction "C_C") (pintype "passive"))
      (node (ref "IC2") (pin "10") (pinfunction "I1_10") (pintype "input"))
      (node (ref "RN1") (pin "9") (pinfunction "9_9") (pintype "passive"))
    )
    (net (code "80") (name "Net-(IC2D-I0)") (class "Default")
      (node (ref "D8") (pin "A") (pinfunction "A_A") (pintype "passive"))
      (node (ref "IC2") (pin "12") (pinfunction "I0_12") (pintype "input"))
      (node (ref "RN2") (pin "8") (pinfunction "8_8") (pintype "passive"))
    )
    (net (code "81") (name "Net-(IC2D-I1)") (class "Default")
      (node (ref "D7") (pin "C") (pinfunction "C_C") (pintype "passive"))
      (node (ref "IC2") (pin "13") (pinfunction "I1_13") (pintype "input"))
      (node (ref "RN1") (pin "8") (pinfunction "8_8") (pintype "passive"))
    )
    (net (code "82") (name "Net-(IC3A-I0)") (class "Default")
      (node (ref "D15") (pin "A") (pinfunction "A_A") (pintype "passive"))
      (node (ref "IC3") (pin "1") (pinfunction "I0_1") (pintype "input"))
      (node (ref "RN2") (pin "7") (pinfunction "7_7") (pintype "passive"))
    )
    (net (code "83") (name "Net-(IC3A-I1)") (class "Default")
      (node (ref "D16") (pin "C") (pinfunction "C_C") (pintype "passive"))
      (node (ref "IC3") (pin "2") (pinfunction "I1_2") (pintype "input"))
      (node (ref "RN1") (pin "7") (pinfunction "7_7") (pintype "passive"))
    )
    (net (code "84") (name "Net-(IC3B-I0)") (class "Default")
      (node (ref "D9") (pin "A") (pinfunction "A_A") (pintype "passive"))
      (node (ref "IC3") (pin "4") (pinfunction "I0_4") (pintype "input"))
      (node (ref "RN2") (pin "6") (pinfunction "6_6") (pintype "passive"))
    )
    (net (code "85") (name "Net-(IC3B-I1)") (class "Default")
      (node (ref "D10") (pin "C") (pinfunction "C_C") (pintype "passive"))
      (node (ref "IC3") (pin "5") (pinfunction "I1_5") (pintype "input"))
      (node (ref "RN1") (pin "6") (pinfunction "6_6") (pintype "passive"))
    )
    (net (code "86") (name "Net-(IC3C-I0)") (class "Default")
      (node (ref "D11") (pin "A") (pinfunction "A_A") (pintype "passive"))
      (node (ref "IC3") (pin "9") (pinfunction "I0_9") (pintype "input"))
      (node (ref "RN2") (pin "5") (pinfunction "5_5") (pintype "passive"))
    )
    (net (code "87") (name "Net-(IC3C-I1)") (class "Default")
      (node (ref "D12") (pin "C") (pinfunction "C_C") (pintype "passive"))
      (node (ref "IC3") (pin "10") (pinfunction "I1_10") (pintype "input"))
      (node (ref "RN1") (pin "5") (pinfunction "5_5") (pintype "passive"))
    )
    (net (code "88") (name "Net-(IC3D-I0)") (class "Default")
      (node (ref "D13") (pin "A") (pinfunction "A_A") (pintype "passive"))
      (node (ref "IC3") (pin "12") (pinfunction "I0_12") (pintype "input"))
      (node (ref "RN2") (pin "4") (pinfunction "4_4") (pintype "passive"))
    )
    (net (code "89") (name "Net-(IC3D-I1)") (class "Default")
      (node (ref "D14") (pin "C") (pinfunction "C_C") (pintype "passive"))
      (node (ref "IC3") (pin "13") (pinfunction "I1_13") (pintype "input"))
      (node (ref "RN1") (pin "4") (pinfunction "4_4") (pintype "passive"))
    )
    (net (code "90") (name "Net-(IC4A-I)") (class "Default")
      (node (ref "IC4") (pin "2") (pinfunction "I_2") (pintype "input"))
      (node (ref "OUT3-4") (pin "2") (pinfunction "2_2") (pintype "passive"))
    )
    (net (code "91") (name "Net-(IC4A-OE)") (class "Default")
      (node (ref "IC4") (pin "1") (pinfunction "OE_1") (pintype "input"))
      (node (ref "OUT3-4") (pin "4") (pinfunction "4_4") (pintype "passive"))
    )
    (net (code "92") (name "Net-(IC4B-I)") (class "Default")
      (node (ref "IC4") (pin "5") (pinfunction "I_5") (pintype "input"))
      (node (ref "OUT3-4") (pin "1") (pinfunction "1_1") (pintype "passive"))
    )
    (net (code "93") (name "Net-(IC4B-OE)") (class "Default")
      (node (ref "IC4") (pin "4") (pinfunction "OE_4") (pintype "input"))
      (node (ref "OUT3-4") (pin "3") (pinfunction "3_3") (pintype "passive"))
    )
    (net (code "94") (name "Net-(IC4C-I)") (class "Default")
      (node (ref "IC4") (pin "9") (pinfunction "I_9") (pintype "input"))
      (node (ref "OUT3-4") (pin "6") (pinfunction "6_6") (pintype "passive"))
    )
    (net (code "95") (name "Net-(IC4C-OE)") (class "Default")
      (node (ref "IC4") (pin "10") (pinfunction "OE_10") (pintype "input"))
      (node (ref "OUT3-4") (pin "8") (pinfunction "8_8") (pintype "passive"))
    )
    (net (code "96") (name "Net-(IC4D-I)") (class "Default")
      (node (ref "IC4") (pin "12") (pinfunction "I_12") (pintype "input"))
      (node (ref "OUT3-4") (pin "5") (pinfunction "5_5") (pintype "passive"))
    )
    (net (code "97") (name "Net-(IC4D-OE)") (class "Default")
      (node (ref "IC4") (pin "13") (pinfunction "OE_13") (pintype "input"))
      (node (ref "OUT3-4") (pin "7") (pinfunction "7_7") (pintype "passive"))
    )
    (net (code "98") (name "Net-(IC5A-I)") (class "Default")
      (node (ref "IC5") (pin "2") (pinfunction "I_2") (pintype "input"))
      (node (ref "OUT3-4") (pin "10") (pinfunction "10_10") (pintype "passive"))
    )
    (net (code "99") (name "Net-(IC5A-OE)") (class "Default")
      (node (ref "IC5") (pin "1") (pinfunction "OE_1") (pintype "input"))
      (node (ref "OUT3-4") (pin "12") (pinfunction "12_12") (pintype "passive"))
    )
    (net (code "100") (name "Net-(IC5B-I)") (class "Default")
      (node (ref "IC5") (pin "5") (pinfunction "I_5") (pintype "input"))
      (node (ref "OUT3-4") (pin "9") (pinfunction "9_9") (pintype "passive"))
    )
    (net (code "101") (name "Net-(IC5B-OE)") (class "Default")
      (node (ref "IC5") (pin "4") (pinfunction "OE_4") (pintype "input"))
      (node (ref "OUT3-4") (pin "11") (pinfunction "11_11") (pintype "passive"))
    )
    (net (code "102") (name "Net-(IC5C-I)") (class "Default")
      (node (ref "IC5") (pin "9") (pinfunction "I_9") (pintype "input"))
      (node (ref "OUT3-4") (pin "14") (pinfunction "14_14") (pintype "passive"))
    )
    (net (code "103") (name "Net-(IC5C-OE)") (class "Default")
      (node (ref "IC5") (pin "10") (pinfunction "OE_10") (pintype "input"))
      (node (ref "OUT3-4") (pin "16") (pinfunction "16_16") (pintype "passive"))
    )
    (net (code "104") (name "Net-(IC5D-I)") (class "Default")
      (node (ref "IC5") (pin "12") (pinfunction "I_12") (pintype "input"))
      (node (ref "OUT3-4") (pin "13") (pinfunction "13_13") (pintype "passive"))
    )
    (net (code "105") (name "Net-(IC5D-OE)") (class "Default")
      (node (ref "IC5") (pin "13") (pinfunction "OE_13") (pintype "input"))
      (node (ref "OUT3-4") (pin "15") (pinfunction "15_15") (pintype "passive"))
    )
    (net (code "106") (name "Net-(IC6A-I)") (class "Default")
      (node (ref "IC6") (pin "2") (pinfunction "I_2") (pintype "input"))
      (node (ref "OUT5-6") (pin "2") (pinfunction "2_2") (pintype "passive"))
    )
    (net (code "107") (name "Net-(IC6A-OE)") (class "Default")
      (node (ref "IC6") (pin "1") (pinfunction "OE_1") (pintype "input"))
      (node (ref "OUT5-6") (pin "4") (pinfunction "4_4") (pintype "passive"))
    )
    (net (code "108") (name "Net-(IC6B-I)") (class "Default")
      (node (ref "IC6") (pin "5") (pinfunction "I_5") (pintype "input"))
      (node (ref "OUT5-6") (pin "1") (pinfunction "1_1") (pintype "passive"))
    )
    (net (code "109") (name "Net-(IC6B-OE)") (class "Default")
      (node (ref "IC6") (pin "4") (pinfunction "OE_4") (pintype "input"))
      (node (ref "OUT5-6") (pin "3") (pinfunction "3_3") (pintype "passive"))
    )
    (net (code "110") (name "Net-(IC6C-I)") (class "Default")
      (node (ref "IC6") (pin "9") (pinfunction "I_9") (pintype "input"))
      (node (ref "OUT5-6") (pin "6") (pinfunction "6_6") (pintype "passive"))
    )
    (net (code "111") (name "Net-(IC6C-OE)") (class "Default")
      (node (ref "IC6") (pin "10") (pinfunction "OE_10") (pintype "input"))
      (node (ref "OUT5-6") (pin "8") (pinfunction "8_8") (pintype "passive"))
    )
    (net (code "112") (name "Net-(IC6D-I)") (class "Default")
      (node (ref "IC6") (pin "12") (pinfunction "I_12") (pintype "input"))
      (node (ref "OUT5-6") (pin "5") (pinfunction "5_5") (pintype "passive"))
    )
    (net (code "113") (name "Net-(IC6D-OE)") (class "Default")
      (node (ref "IC6") (pin "13") (pinfunction "OE_13") (pintype "input"))
      (node (ref "OUT5-6") (pin "7") (pinfunction "7_7") (pintype "passive"))
    )
    (net (code "114") (name "Net-(IC7A-I)") (class "Default")
      (node (ref "IC7") (pin "2") (pinfunction "I_2") (pintype "input"))
      (node (ref "OUT5-6") (pin "10") (pinfunction "10_10") (pintype "passive"))
    )
    (net (code "115") (name "Net-(IC7A-OE)") (class "Default")
      (node (ref "IC7") (pin "1") (pinfunction "OE_1") (pintype "input"))
      (node (ref "OUT5-6") (pin "12") (pinfunction "12_12") (pintype "passive"))
    )
    (net (code "116") (name "Net-(IC7B-I)") (class "Default")
      (node (ref "IC7") (pin "5") (pinfunction "I_5") (pintype "input"))
      (node (ref "OUT5-6") (pin "9") (pinfunction "9_9") (pintype "passive"))
    )
    (net (code "117") (name "Net-(IC7B-OE)") (class "Default")
      (node (ref "IC7") (pin "4") (pinfunction "OE_4") (pintype "input"))
      (node (ref "OUT5-6") (pin "11") (pinfunction "11_11") (pintype "passive"))
    )
    (net (code "118") (name "Net-(IC7C-I)") (class "Default")
      (node (ref "IC7") (pin "9") (pinfunction "I_9") (pintype "input"))
      (node (ref "OUT5-6") (pin "14") (pinfunction "14_14") (pintype "passive"))
    )
    (net (code "119") (name "Net-(IC7C-OE)") (class "Default")
      (node (ref "IC7") (pin "10") (pinfunction "OE_10") (pintype "input"))
      (node (ref "OUT5-6") (pin "16") (pinfunction "16_16") (pintype "passive"))
    )
    (net (code "120") (name "Net-(IC7D-I)") (class "Default")
      (node (ref "IC7") (pin "12") (pinfunction "I_12") (pintype "input"))
      (node (ref "OUT5-6") (pin "13") (pinfunction "13_13") (pintype "passive"))
    )
    (net (code "121") (name "Net-(IC7D-OE)") (class "Default")
      (node (ref "IC7") (pin "13") (pinfunction "OE_13") (pintype "input"))
      (node (ref "OUT5-6") (pin "15") (pinfunction "15_15") (pintype "passive"))
    )
    (net (code "122") (name "Net-(IC8A-I)") (class "Default")
      (node (ref "IC8") (pin "2") (pinfunction "I_2") (pintype "input"))
      (node (ref "OUT7-8") (pin "2") (pinfunction "2_2") (pintype "passive"))
    )
    (net (code "123") (name "Net-(IC8A-OE)") (class "Default")
      (node (ref "IC8") (pin "1") (pinfunction "OE_1") (pintype "input"))
      (node (ref "OUT7-8") (pin "4") (pinfunction "4_4") (pintype "passive"))
    )
    (net (code "124") (name "Net-(IC8B-I)") (class "Default")
      (node (ref "IC8") (pin "5") (pinfunction "I_5") (pintype "input"))
      (node (ref "OUT7-8") (pin "1") (pinfunction "1_1") (pintype "passive"))
    )
    (net (code "125") (name "Net-(IC8B-OE)") (class "Default")
      (node (ref "IC8") (pin "4") (pinfunction "OE_4") (pintype "input"))
      (node (ref "OUT7-8") (pin "3") (pinfunction "3_3") (pintype "passive"))
    )
    (net (code "126") (name "Net-(IC8C-I)") (class "Default")
      (node (ref "IC8") (pin "9") (pinfunction "I_9") (pintype "input"))
      (node (ref "OUT7-8") (pin "6") (pinfunction "6_6") (pintype "passive"))
    )
    (net (code "127") (name "Net-(IC8C-OE)") (class "Default")
      (node (ref "IC8") (pin "10") (pinfunction "OE_10") (pintype "input"))
      (node (ref "OUT7-8") (pin "8") (pinfunction "8_8") (pintype "passive"))
    )
    (net (code "128") (name "Net-(IC8D-I)") (class "Default")
      (node (ref "IC8") (pin "12") (pinfunction "I_12") (pintype "input"))
      (node (ref "OUT7-8") (pin "5") (pinfunction "5_5") (pintype "passive"))
    )
    (net (code "129") (name "Net-(IC8D-OE)") (class "Default")
      (node (ref "IC8") (pin "13") (pinfunction "OE_13") (pintype "input"))
      (node (ref "OUT7-8") (pin "7") (pinfunction "7_7") (pintype "passive"))
    )
    (net (code "130") (name "Net-(IC9A-I0)") (class "Default")
      (node (ref "D23") (pin "A") (pinfunction "A_A") (pintype "passive"))
      (node (ref "IC9") (pin "1") (pinfunction "I0_1") (pintype "input"))
      (node (ref "RN3") (pin "11") (pinfunction "11_11") (pintype "passive"))
    )
    (net (code "131") (name "Net-(IC9A-I1)") (class "Default")
      (node (ref "D24") (pin "C") (pinfunction "C_C") (pintype "passive"))
      (node (ref "IC9") (pin "2") (pinfunction "I1_2") (pintype "input"))
      (node (ref "RN4") (pin "11") (pinfunction "11_11") (pintype "passive"))
    )
    (net (code "132") (name "Net-(IC9B-I0)") (class "Default")
      (node (ref "D17") (pin "A") (pinfunction "A_A") (pintype "passive"))
      (node (ref "IC9") (pin "4") (pinfunction "I0_4") (pintype "input"))
      (node (ref "RN3") (pin "10") (pinfunction "10_10") (pintype "passive"))
    )
    (net (code "133") (name "Net-(IC9B-I1)") (class "Default")
      (node (ref "D18") (pin "C") (pinfunction "C_C") (pintype "passive"))
      (node (ref "IC9") (pin "5") (pinfunction "I1_5") (pintype "input"))
      (node (ref "RN4") (pin "10") (pinfunction "10_10") (pintype "passive"))
    )
    (net (code "134") (name "Net-(IC9C-I0)") (class "Default")
      (node (ref "D19") (pin "A") (pinfunction "A_A") (pintype "passive"))
      (node (ref "IC9") (pin "9") (pinfunction "I0_9") (pintype "input"))
      (node (ref "RN3") (pin "9") (pinfunction "9_9") (pintype "passive"))
    )
    (net (code "135") (name "Net-(IC9C-I1)") (class "Default")
      (node (ref "D20") (pin "C") (pinfunction "C_C") (pintype "passive"))
      (node (ref "IC9") (pin "10") (pinfunction "I1_10") (pintype "input"))
      (node (ref "RN4") (pin "9") (pinfunction "9_9") (pintype "passive"))
    )
    (net (code "136") (name "Net-(IC9D-I0)") (class "Default")
      (node (ref "D21") (pin "A") (pinfunction "A_A") (pintype "passive"))
      (node (ref "IC9") (pin "12") (pinfunction "I0_12") (pintype "input"))
      (node (ref "RN3") (pin "8") (pinfunction "8_8") (pintype "passive"))
    )
    (net (code "137") (name "Net-(IC9D-I1)") (class "Default")
      (node (ref "D22") (pin "C") (pinfunction "C_C") (pintype "passive"))
      (node (ref "IC9") (pin "13") (pinfunction "I1_13") (pintype "input"))
      (node (ref "RN4") (pin "8") (pinfunction "8_8") (pintype "passive"))
    )
    (net (code "138") (name "Net-(IC10A-I0)") (class "Default")
      (node (ref "D31") (pin "A") (pinfunction "A_A") (pintype "passive"))
      (node (ref "IC10") (pin "1") (pinfunction "I0_1") (pintype "input"))
      (node (ref "RN3") (pin "7") (pinfunction "7_7") (pintype "passive"))
    )
    (net (code "139") (name "Net-(IC10A-I1)") (class "Default")
      (node (ref "D32") (pin "C") (pinfunction "C_C") (pintype "passive"))
      (node (ref "IC10") (pin "2") (pinfunction "I1_2") (pintype "input"))
      (node (ref "RN4") (pin "7") (pinfunction "7_7") (pintype "passive"))
    )
    (net (code "140") (name "Net-(IC10B-I0)") (class "Default")
      (node (ref "D25") (pin "A") (pinfunction "A_A") (pintype "passive"))
      (node (ref "IC10") (pin "4") (pinfunction "I0_4") (pintype "input"))
      (node (ref "RN3") (pin "6") (pinfunction "6_6") (pintype "passive"))
    )
    (net (code "141") (name "Net-(IC10B-I1)") (class "Default")
      (node (ref "D26") (pin "C") (pinfunction "C_C") (pintype "passive"))
      (node (ref "IC10") (pin "5") (pinfunction "I1_5") (pintype "input"))
      (node (ref "RN4") (pin "6") (pinfunction "6_6") (pintype "passive"))
    )
    (net (code "142") (name "Net-(IC10C-I0)") (class "Default")
      (node (ref "D27") (pin "A") (pinfunction "A_A") (pintype "passive"))
      (node (ref "IC10") (pin "9") (pinfunction "I0_9") (pintype "input"))
      (node (ref "RN3") (pin "5") (pinfunction "5_5") (pintype "passive"))
    )
    (net (code "143") (name "Net-(IC10C-I1)") (class "Default")
      (node (ref "D28") (pin "C") (pinfunction "C_C") (pintype "passive"))
      (node (ref "IC10") (pin "10") (pinfunction "I1_10") (pintype "input"))
      (node (ref "RN4") (pin "5") (pinfunction "5_5") (pintype "passive"))
    )
    (net (code "144") (name "Net-(IC10D-I0)") (class "Default")
      (node (ref "D29") (pin "A") (pinfunction "A_A") (pintype "passive"))
      (node (ref "IC10") (pin "12") (pinfunction "I0_12") (pintype "input"))
      (node (ref "RN3") (pin "4") (pinfunction "4_4") (pintype "passive"))
    )
    (net (code "145") (name "Net-(IC10D-I1)") (class "Default")
      (node (ref "D30") (pin "C") (pinfunction "C_C") (pintype "passive"))
      (node (ref "IC10") (pin "13") (pinfunction "I1_13") (pintype "input"))
      (node (ref "RN4") (pin "4") (pinfunction "4_4") (pintype "passive"))
    )
    (net (code "146") (name "Net-(IC11A-I0)") (class "Default")
      (node (ref "D39") (pin "A") (pinfunction "A_A") (pintype "passive"))
      (node (ref "IC11") (pin "1") (pinfunction "I0_1") (pintype "input"))
      (node (ref "RN5") (pin "11") (pinfunction "11_11") (pintype "passive"))
    )
    (net (code "147") (name "Net-(IC11A-I1)") (class "Default")
      (node (ref "D40") (pin "C") (pinfunction "C_C") (pintype "passive"))
      (node (ref "IC11") (pin "2") (pinfunction "I1_2") (pintype "input"))
      (node (ref "RN6") (pin "11") (pinfunction "11_11") (pintype "passive"))
    )
    (net (code "148") (name "Net-(IC11B-I0)") (class "Default")
      (node (ref "D33") (pin "A") (pinfunction "A_A") (pintype "passive"))
      (node (ref "IC11") (pin "4") (pinfunction "I0_4") (pintype "input"))
      (node (ref "RN5") (pin "10") (pinfunction "10_10") (pintype "passive"))
    )
    (net (code "149") (name "Net-(IC11B-I1)") (class "Default")
      (node (ref "D34") (pin "C") (pinfunction "C_C") (pintype "passive"))
      (node (ref "IC11") (pin "5") (pinfunction "I1_5") (pintype "input"))
      (node (ref "RN6") (pin "10") (pinfunction "10_10") (pintype "passive"))
    )
    (net (code "150") (name "Net-(IC11C-I0)") (class "Default")
      (node (ref "D35") (pin "A") (pinfunction "A_A") (pintype "passive"))
      (node (ref "IC11") (pin "9") (pinfunction "I0_9") (pintype "input"))
      (node (ref "RN5") (pin "9") (pinfunction "9_9") (pintype "passive"))
    )
    (net (code "151") (name "Net-(IC11C-I1)") (class "Default")
      (node (ref "D36") (pin "C") (pinfunction "C_C") (pintype "passive"))
      (node (ref "IC11") (pin "10") (pinfunction "I1_10") (pintype "input"))
      (node (ref "RN6") (pin "9") (pinfunction "9_9") (pintype "passive"))
    )
    (net (code "152") (name "Net-(IC11D-I0)") (class "Default")
      (node (ref "D37") (pin "A") (pinfunction "A_A") (pintype "passive"))
      (node (ref "IC11") (pin "12") (pinfunction "I0_12") (pintype "input"))
      (node (ref "RN5") (pin "8") (pinfunction "8_8") (pintype "passive"))
    )
    (net (code "153") (name "Net-(IC11D-I1)") (class "Default")
      (node (ref "D38") (pin "C") (pinfunction "C_C") (pintype "passive"))
      (node (ref "IC11") (pin "13") (pinfunction "I1_13") (pintype "input"))
      (node (ref "RN6") (pin "8") (pinfunction "8_8") (pintype "passive"))
    )
    (net (code "154") (name "Net-(IC12A-I0)") (class "Default")
      (node (ref "D47") (pin "A") (pinfunction "A_A") (pintype "passive"))
      (node (ref "IC12") (pin "1") (pinfunction "I0_1") (pintype "input"))
      (node (ref "RN5") (pin "7") (pinfunction "7_7") (pintype "passive"))
    )
    (net (code "155") (name "Net-(IC12A-I1)") (class "Default")
      (node (ref "D48") (pin "C") (pinfunction "C_C") (pintype "passive"))
      (node (ref "IC12") (pin "2") (pinfunction "I1_2") (pintype "input"))
      (node (ref "RN6") (pin "7") (pinfunction "7_7") (pintype "passive"))
    )
    (net (code "156") (name "Net-(IC12B-I0)") (class "Default")
      (node (ref "D41") (pin "A") (pinfunction "A_A") (pintype "passive"))
      (node (ref "IC12") (pin "4") (pinfunction "I0_4") (pintype "input"))
      (node (ref "RN5") (pin "6") (pinfunction "6_6") (pintype "passive"))
    )
    (net (code "157") (name "Net-(IC12B-I1)") (class "Default")
      (node (ref "D42") (pin "C") (pinfunction "C_C") (pintype "passive"))
      (node (ref "IC12") (pin "5") (pinfunction "I1_5") (pintype "input"))
      (node (ref "RN6") (pin "6") (pinfunction "6_6") (pintype "passive"))
    )
    (net (code "158") (name "Net-(IC12C-I0)") (class "Default")
      (node (ref "D43") (pin "A") (pinfunction "A_A") (pintype "passive"))
      (node (ref "IC12") (pin "9") (pinfunction "I0_9") (pintype "input"))
      (node (ref "RN5") (pin "5") (pinfunction "5_5") (pintype "passive"))
    )
    (net (code "159") (name "Net-(IC12C-I1)") (class "Default")
      (node (ref "D44") (pin "C") (pinfunction "C_C") (pintype "passive"))
      (node (ref "IC12") (pin "10") (pinfunction "I1_10") (pintype "input"))
      (node (ref "RN6") (pin "5") (pinfunction "5_5") (pintype "passive"))
    )
    (net (code "160") (name "Net-(IC12D-I0)") (class "Default")
      (node (ref "D45") (pin "A") (pinfunction "A_A") (pintype "passive"))
      (node (ref "IC12") (pin "12") (pinfunction "I0_12") (pintype "input"))
      (node (ref "RN5") (pin "4") (pinfunction "4_4") (pintype "passive"))
    )
    (net (code "161") (name "Net-(IC12D-I1)") (class "Default")
      (node (ref "D46") (pin "C") (pinfunction "C_C") (pintype "passive"))
      (node (ref "IC12") (pin "13") (pinfunction "I1_13") (pintype "input"))
      (node (ref "RN6") (pin "4") (pinfunction "4_4") (pintype "passive"))
    )
    (net (code "162") (name "Net-(IC13A-I0)") (class "Default")
      (node (ref "D55") (pin "A") (pinfunction "A_A") (pintype "passive"))
      (node (ref "IC13") (pin "1") (pinfunction "I0_1") (pintype "input"))
      (node (ref "RN7") (pin "11") (pinfunction "11_11") (pintype "passive"))
    )
    (net (code "163") (name "Net-(IC13A-I1)") (class "Default")
      (node (ref "D56") (pin "C") (pinfunction "C_C") (pintype "passive"))
      (node (ref "IC13") (pin "2") (pinfunction "I1_2") (pintype "input"))
      (node (ref "RN8") (pin "11") (pinfunction "11_11") (pintype "passive"))
    )
    (net (code "164") (name "Net-(IC13B-I0)") (class "Default")
      (node (ref "D49") (pin "A") (pinfunction "A_A") (pintype "passive"))
      (node (ref "IC13") (pin "4") (pinfunction "I0_4") (pintype "input"))
      (node (ref "RN7") (pin "10") (pinfunction "10_10") (pintype "passive"))
    )
    (net (code "165") (name "Net-(IC13B-I1)") (class "Default")
      (node (ref "D50") (pin "C") (pinfunction "C_C") (pintype "passive"))
      (node (ref "IC13") (pin "5") (pinfunction "I1_5") (pintype "input"))
      (node (ref "RN8") (pin "10") (pinfunction "10_10") (pintype "passive"))
    )
    (net (code "166") (name "Net-(IC13C-I0)") (class "Default")
      (node (ref "D51") (pin "A") (pinfunction "A_A") (pintype "passive"))
      (node (ref "IC13") (pin "9") (pinfunction "I0_9") (pintype "input"))
      (node (ref "RN7") (pin "9") (pinfunction "9_9") (pintype "passive"))
    )
    (net (code "167") (name "Net-(IC13C-I1)") (class "Default")
      (node (ref "D52") (pin "C") (pinfunction "C_C") (pintype "passive"))
      (node (ref "IC13") (pin "10") (pinfunction "I1_10") (pintype "input"))
      (node (ref "RN8") (pin "9") (pinfunction "9_9") (pintype "passive"))
    )
    (net (code "168") (name "Net-(IC13D-I0)") (class "Default")
      (node (ref "D53") (pin "A") (pinfunction "A_A") (pintype "passive"))
      (node (ref "IC13") (pin "12") (pinfunction "I0_12") (pintype "input"))
      (node (ref "RN7") (pin "8") (pinfunction "8_8") (pintype "passive"))
    )
    (net (code "169") (name "Net-(IC13D-I1)") (class "Default")
      (node (ref "D54") (pin "C") (pinfunction "C_C") (pintype "passive"))
      (node (ref "IC13") (pin "13") (pinfunction "I1_13") (pintype "input"))
      (node (ref "RN8") (pin "8") (pinfunction "8_8") (pintype "passive"))
    )
    (net (code "170") (name "Net-(IC14A-I0)") (class "Default")
      (node (ref "D63") (pin "A") (pinfunction "A_A") (pintype "passive"))
      (node (ref "IC14") (pin "1") (pinfunction "I0_1") (pintype "input"))
      (node (ref "RN7") (pin "7") (pinfunction "7_7") (pintype "passive"))
    )
    (net (code "171") (name "Net-(IC14A-I1)") (class "Default")
      (node (ref "D64") (pin "C") (pinfunction "C_C") (pintype "passive"))
      (node (ref "IC14") (pin "2") (pinfunction "I1_2") (pintype "input"))
      (node (ref "RN8") (pin "7") (pinfunction "7_7") (pintype "passive"))
    )
    (net (code "172") (name "Net-(IC14B-I0)") (class "Default")
      (node (ref "D57") (pin "A") (pinfunction "A_A") (pintype "passive"))
      (node (ref "IC14") (pin "4") (pinfunction "I0_4") (pintype "input"))
      (node (ref "RN7") (pin "6") (pinfunction "6_6") (pintype "passive"))
    )
    (net (code "173") (name "Net-(IC14B-I1)") (class "Default")
      (node (ref "D58") (pin "C") (pinfunction "C_C") (pintype "passive"))
      (node (ref "IC14") (pin "5") (pinfunction "I1_5") (pintype "input"))
      (node (ref "RN8") (pin "6") (pinfunction "6_6") (pintype "passive"))
    )
    (net (code "174") (name "Net-(IC14C-I0)") (class "Default")
      (node (ref "D59") (pin "A") (pinfunction "A_A") (pintype "passive"))
      (node (ref "IC14") (pin "9") (pinfunction "I0_9") (pintype "input"))
      (node (ref "RN7") (pin "5") (pinfunction "5_5") (pintype "passive"))
    )
    (net (code "175") (name "Net-(IC14C-I1)") (class "Default")
      (node (ref "D60") (pin "C") (pinfunction "C_C") (pintype "passive"))
      (node (ref "IC14") (pin "10") (pinfunction "I1_10") (pintype "input"))
      (node (ref "RN8") (pin "5") (pinfunction "5_5") (pintype "passive"))
    )
    (net (code "176") (name "Net-(IC14D-I0)") (class "Default")
      (node (ref "D61") (pin "A") (pinfunction "A_A") (pintype "passive"))
      (node (ref "IC14") (pin "12") (pinfunction "I0_12") (pintype "input"))
      (node (ref "RN7") (pin "4") (pinfunction "4_4") (pintype "passive"))
    )
    (net (code "177") (name "Net-(IC14D-I1)") (class "Default")
      (node (ref "D62") (pin "C") (pinfunction "C_C") (pintype "passive"))
      (node (ref "IC14") (pin "13") (pinfunction "I1_13") (pintype "input"))
      (node (ref "RN8") (pin "4") (pinfunction "4_4") (pintype "passive"))
    )
    (net (code "178") (name "Net-(IC20A-I)") (class "Default")
      (node (ref "IC20") (pin "2") (pinfunction "I_2") (pintype "input"))
      (node (ref "OUT1-2") (pin "2") (pinfunction "2_2") (pintype "passive"))
    )
    (net (code "179") (name "Net-(IC20A-OE)") (class "Default")
      (node (ref "IC20") (pin "1") (pinfunction "OE_1") (pintype "input"))
      (node (ref "OUT1-2") (pin "4") (pinfunction "4_4") (pintype "passive"))
    )
    (net (code "180") (name "Net-(IC20B-I)") (class "Default")
      (node (ref "IC20") (pin "5") (pinfunction "I_5") (pintype "input"))
      (node (ref "OUT1-2") (pin "1") (pinfunction "1_1") (pintype "passive"))
    )
    (net (code "181") (name "Net-(IC20B-OE)") (class "Default")
      (node (ref "IC20") (pin "4") (pinfunction "OE_4") (pintype "input"))
      (node (ref "OUT1-2") (pin "3") (pinfunction "3_3") (pintype "passive"))
    )
    (net (code "182") (name "Net-(IC20C-I)") (class "Default")
      (node (ref "IC20") (pin "9") (pinfunction "I_9") (pintype "input"))
      (node (ref "OUT1-2") (pin "6") (pinfunction "6_6") (pintype "passive"))
    )
    (net (code "183") (name "Net-(IC20C-OE)") (class "Default")
      (node (ref "IC20") (pin "10") (pinfunction "OE_10") (pintype "input"))
      (node (ref "OUT1-2") (pin "8") (pinfunction "8_8") (pintype "passive"))
    )
    (net (code "184") (name "Net-(IC20D-I)") (class "Default")
      (node (ref "IC20") (pin "12") (pinfunction "I_12") (pintype "input"))
      (node (ref "OUT1-2") (pin "5") (pinfunction "5_5") (pintype "passive"))
    )
    (net (code "185") (name "Net-(IC20D-OE)") (class "Default")
      (node (ref "IC20") (pin "13") (pinfunction "OE_13") (pintype "input"))
      (node (ref "OUT1-2") (pin "7") (pinfunction "7_7") (pintype "passive"))
    )
    (net (code "186") (name "Net-(IC21A-I)") (class "Default")
      (node (ref "IC21") (pin "2") (pinfunction "I_2") (pintype "input"))
      (node (ref "OUT7-8") (pin "10") (pinfunction "10_10") (pintype "passive"))
    )
    (net (code "187") (name "Net-(IC21A-OE)") (class "Default")
      (node (ref "IC21") (pin "1") (pinfunction "OE_1") (pintype "input"))
      (node (ref "OUT7-8") (pin "12") (pinfunction "12_12") (pintype "passive"))
    )
    (net (code "188") (name "Net-(IC21B-I)") (class "Default")
      (node (ref "IC21") (pin "5") (pinfunction "I_5") (pintype "input"))
      (node (ref "OUT7-8") (pin "9") (pinfunction "9_9") (pintype "passive"))
    )
    (net (code "189") (name "Net-(IC21B-OE)") (class "Default")
      (node (ref "IC21") (pin "4") (pinfunction "OE_4") (pintype "input"))
      (node (ref "OUT7-8") (pin "11") (pinfunction "11_11") (pintype "passive"))
    )
    (net (code "190") (name "Net-(IC21C-I)") (class "Default")
      (node (ref "IC21") (pin "9") (pinfunction "I_9") (pintype "input"))
      (node (ref "OUT7-8") (pin "14") (pinfunction "14_14") (pintype "passive"))
    )
    (net (code "191") (name "Net-(IC21C-OE)") (class "Default")
      (node (ref "IC21") (pin "10") (pinfunction "OE_10") (pintype "input"))
      (node (ref "OUT7-8") (pin "16") (pinfunction "16_16") (pintype "passive"))
    )
    (net (code "192") (name "Net-(IC21D-I)") (class "Default")
      (node (ref "IC21") (pin "12") (pinfunction "I_12") (pintype "input"))
      (node (ref "OUT7-8") (pin "13") (pinfunction "13_13") (pintype "passive"))
    )
    (net (code "193") (name "Net-(IC21D-OE)") (class "Default")
      (node (ref "IC21") (pin "13") (pinfunction "OE_13") (pintype "input"))
      (node (ref "OUT7-8") (pin "15") (pinfunction "15_15") (pintype "passive"))
    )
    (net (code "194") (name "VCC") (class "Default")
      (node (ref "BYP1") (pin "1") (pinfunction "1_1") (pintype "passive"))
      (node (ref "BYP11") (pin "1") (pinfunction "1_1") (pintype "passive"))
      (node (ref "BYP12") (pin "1") (pinfunction "1_1") (pintype "passive"))
      (node (ref "BYP13") (pin "1") (pinfunction "1_1") (pintype "passive"))
      (node (ref "BYP14") (pin "1") (pinfunction "1_1") (pintype "passive"))
      (node (ref "BYP15") (pin "1") (pinfunction "1_1") (pintype "passive"))
      (node (ref "BYP16") (pin "1") (pinfunction "1_1") (pintype "passive"))
      (node (ref "BYP18") (pin "1") (pinfunction "1_1") (pintype "passive"))
      (node (ref "BYP19") (pin "1") (pinfunction "1_1") (pintype "passive"))
      (node (ref "BYP2") (pin "1") (pinfunction "1_1") (pintype "passive"))
      (node (ref "BYP20") (pin "1") (pinfunction "1_1") (pintype "passive"))
      (node (ref "BYP3") (pin "1") (pinfunction "1_1") (pintype "passive"))
      (node (ref "BYP4") (pin "1") (pinfunction "1_1") (pintype "passive"))
      (node (ref "BYP5") (pin "1") (pinfunction "1_1") (pintype "passive"))
      (node (ref "BYP6") (pin "1") (pinfunction "1_1") (pintype "passive"))
      (node (ref "BYP7") (pin "1") (pinfunction "1_1") (pintype "passive"))
      (node (ref "BYP8") (pin "1") (pinfunction "1_1") (pintype "passive"))
      (node (ref "JP2") (pin "2") (pinfunction "2_2") (pintype "passive"))
      (node (ref "RN2") (pin "1") (pinfunction "1_1") (pintype "passive"))
      (node (ref "RN3") (pin "1") (pinfunction "1_1") (pintype "passive"))
      (node (ref "RN5") (pin "1") (pinfunction "1_1") (pintype "passive"))
      (node (ref "RN7") (pin "1") (pinfunction "1_1") (pintype "passive"))
      (node (ref "SV2") (pin "2") (pinfunction "2_2") (pintype "passive"))
    )
    (net (code "195") (name "unconnected-(RN1-Pad2)") (class "Default")
      (node (ref "RN1") (pin "2") (pinfunction "2_2") (pintype "passive"))
    )
    (net (code "196") (name "unconnected-(RN1-Pad3)") (class "Default")
      (node (ref "RN1") (pin "3") (pinfunction "3_3") (pintype "passive"))
    )
    (net (code "197") (name "unconnected-(RN2-Pad2)") (class "Default")
      (node (ref "RN2") (pin "2") (pinfunction "2_2") (pintype "passive"))
    )
    (net (code "198") (name "unconnected-(RN2-Pad3)") (class "Default")
      (node (ref "RN2") (pin "3") (pinfunction "3_3") (pintype "passive"))
    )
    (net (code "199") (name "unconnected-(RN3-Pad2)") (class "Default")
      (node (ref "RN3") (pin "2") (pinfunction "2_2") (pintype "passive"))
    )
    (net (code "200") (name "unconnected-(RN3-Pad3)") (class "Default")
      (node (ref "RN3") (pin "3") (pinfunction "3_3") (pintype "passive"))
    )
    (net (code "201") (name "unconnected-(RN4-Pad2)") (class "Default")
      (node (ref "RN4") (pin "2") (pinfunction "2_2") (pintype "passive"))
    )
    (net (code "202") (name "unconnected-(RN4-Pad3)") (class "Default")
      (node (ref "RN4") (pin "3") (pinfunction "3_3") (pintype "passive"))
    )
    (net (code "203") (name "unconnected-(RN5-Pad2)") (class "Default")
      (node (ref "RN5") (pin "2") (pinfunction "2_2") (pintype "passive"))
    )
    (net (code "204") (name "unconnected-(RN5-Pad3)") (class "Default")
      (node (ref "RN5") (pin "3") (pinfunction "3_3") (pintype "passive"))
    )
    (net (code "205") (name "unconnected-(RN6-Pad2)") (class "Default")
      (node (ref "RN6") (pin "2") (pinfunction "2_2") (pintype "passive"))
    )
    (net (code "206") (name "unconnected-(RN6-Pad3)") (class "Default")
      (node (ref "RN6") (pin "3") (pinfunction "3_3") (pintype "passive"))
    )
    (net (code "207") (name "unconnected-(RN7-Pad2)") (class "Default")
      (node (ref "RN7") (pin "2") (pinfunction "2_2") (pintype "passive"))
    )
    (net (code "208") (name "unconnected-(RN7-Pad3)") (class "Default")
      (node (ref "RN7") (pin "3") (pinfunction "3_3") (pintype "passive"))
    )
    (net (code "209") (name "unconnected-(RN8-Pad2)") (class "Default")
      (node (ref "RN8") (pin "2") (pinfunction "2_2") (pintype "passive"))
    )
    (net (code "210") (name "unconnected-(RN8-Pad3)") (class "Default")
      (node (ref "RN8") (pin "3") (pinfunction "3_3") (pintype "passive"))
    )
    (net (code "211") (name "unconnected-(SV2-Pad4)") (class "Default")
      (node (ref "SV2") (pin "4") (pinfunction "4_4") (pintype "passive"))
    )
  )
)
